# Cube_Robot.net
KiCad netlist of a schematic drawn in Altium Designer
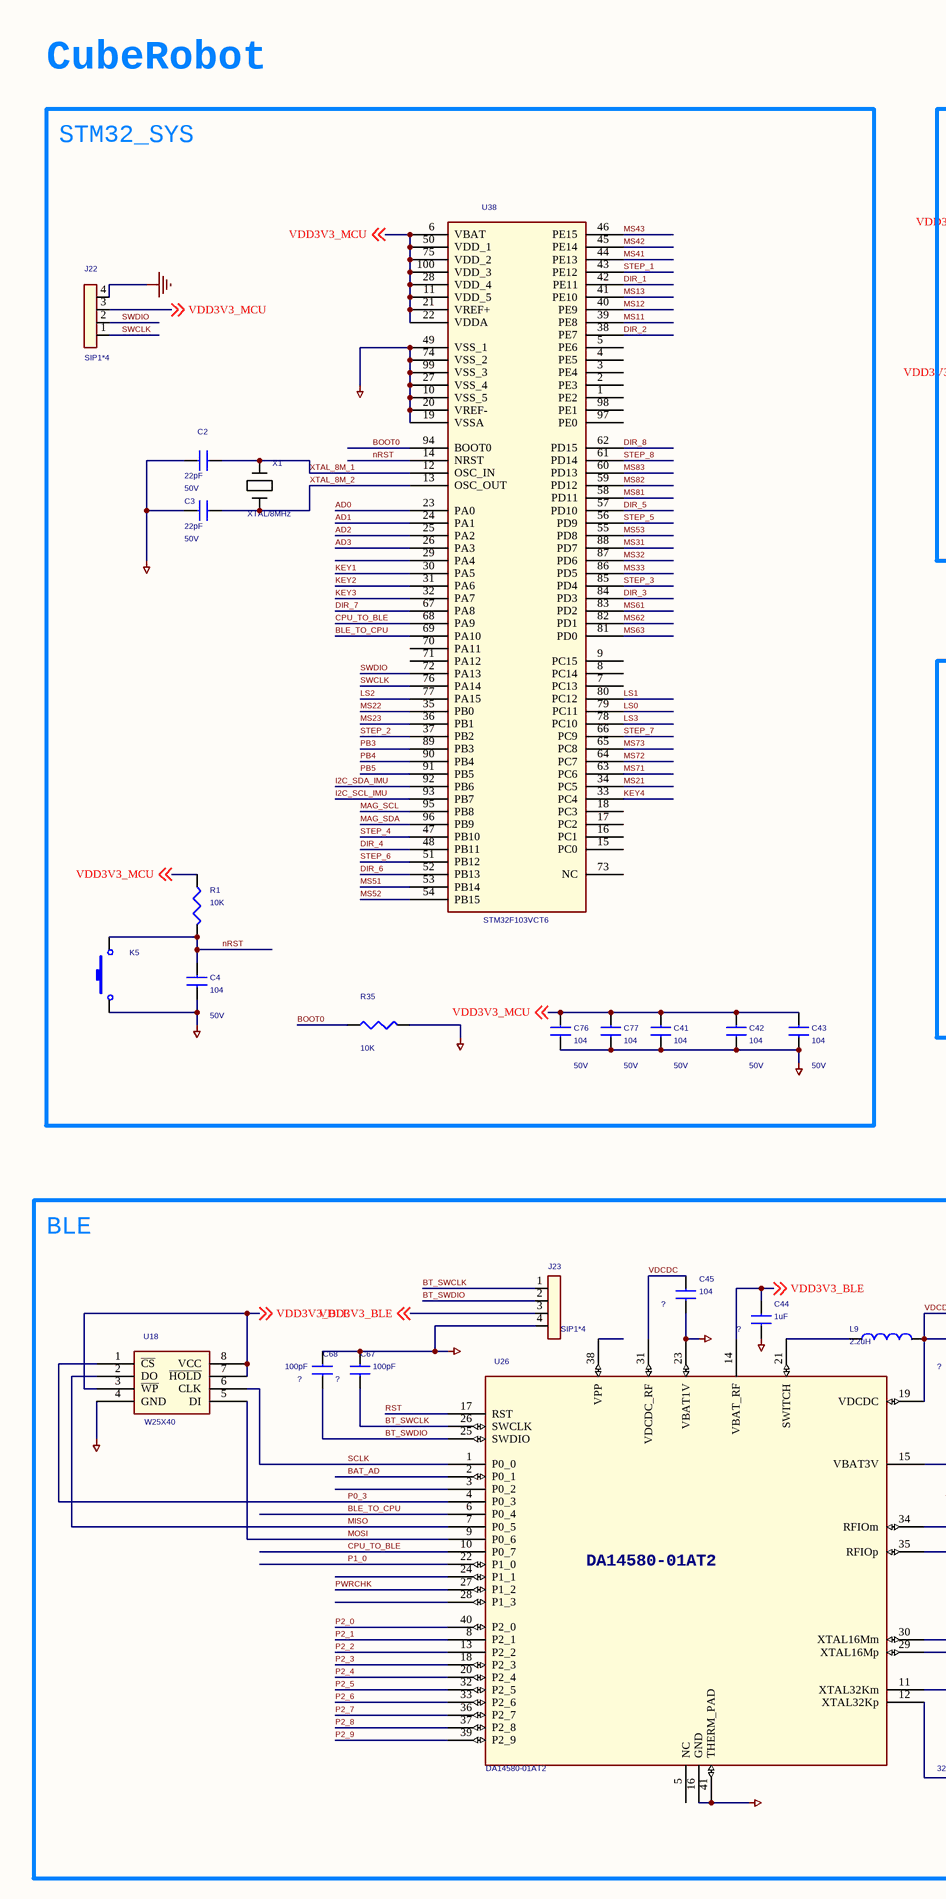
[diagram p0: Cube_Robot.SchDoc, left]
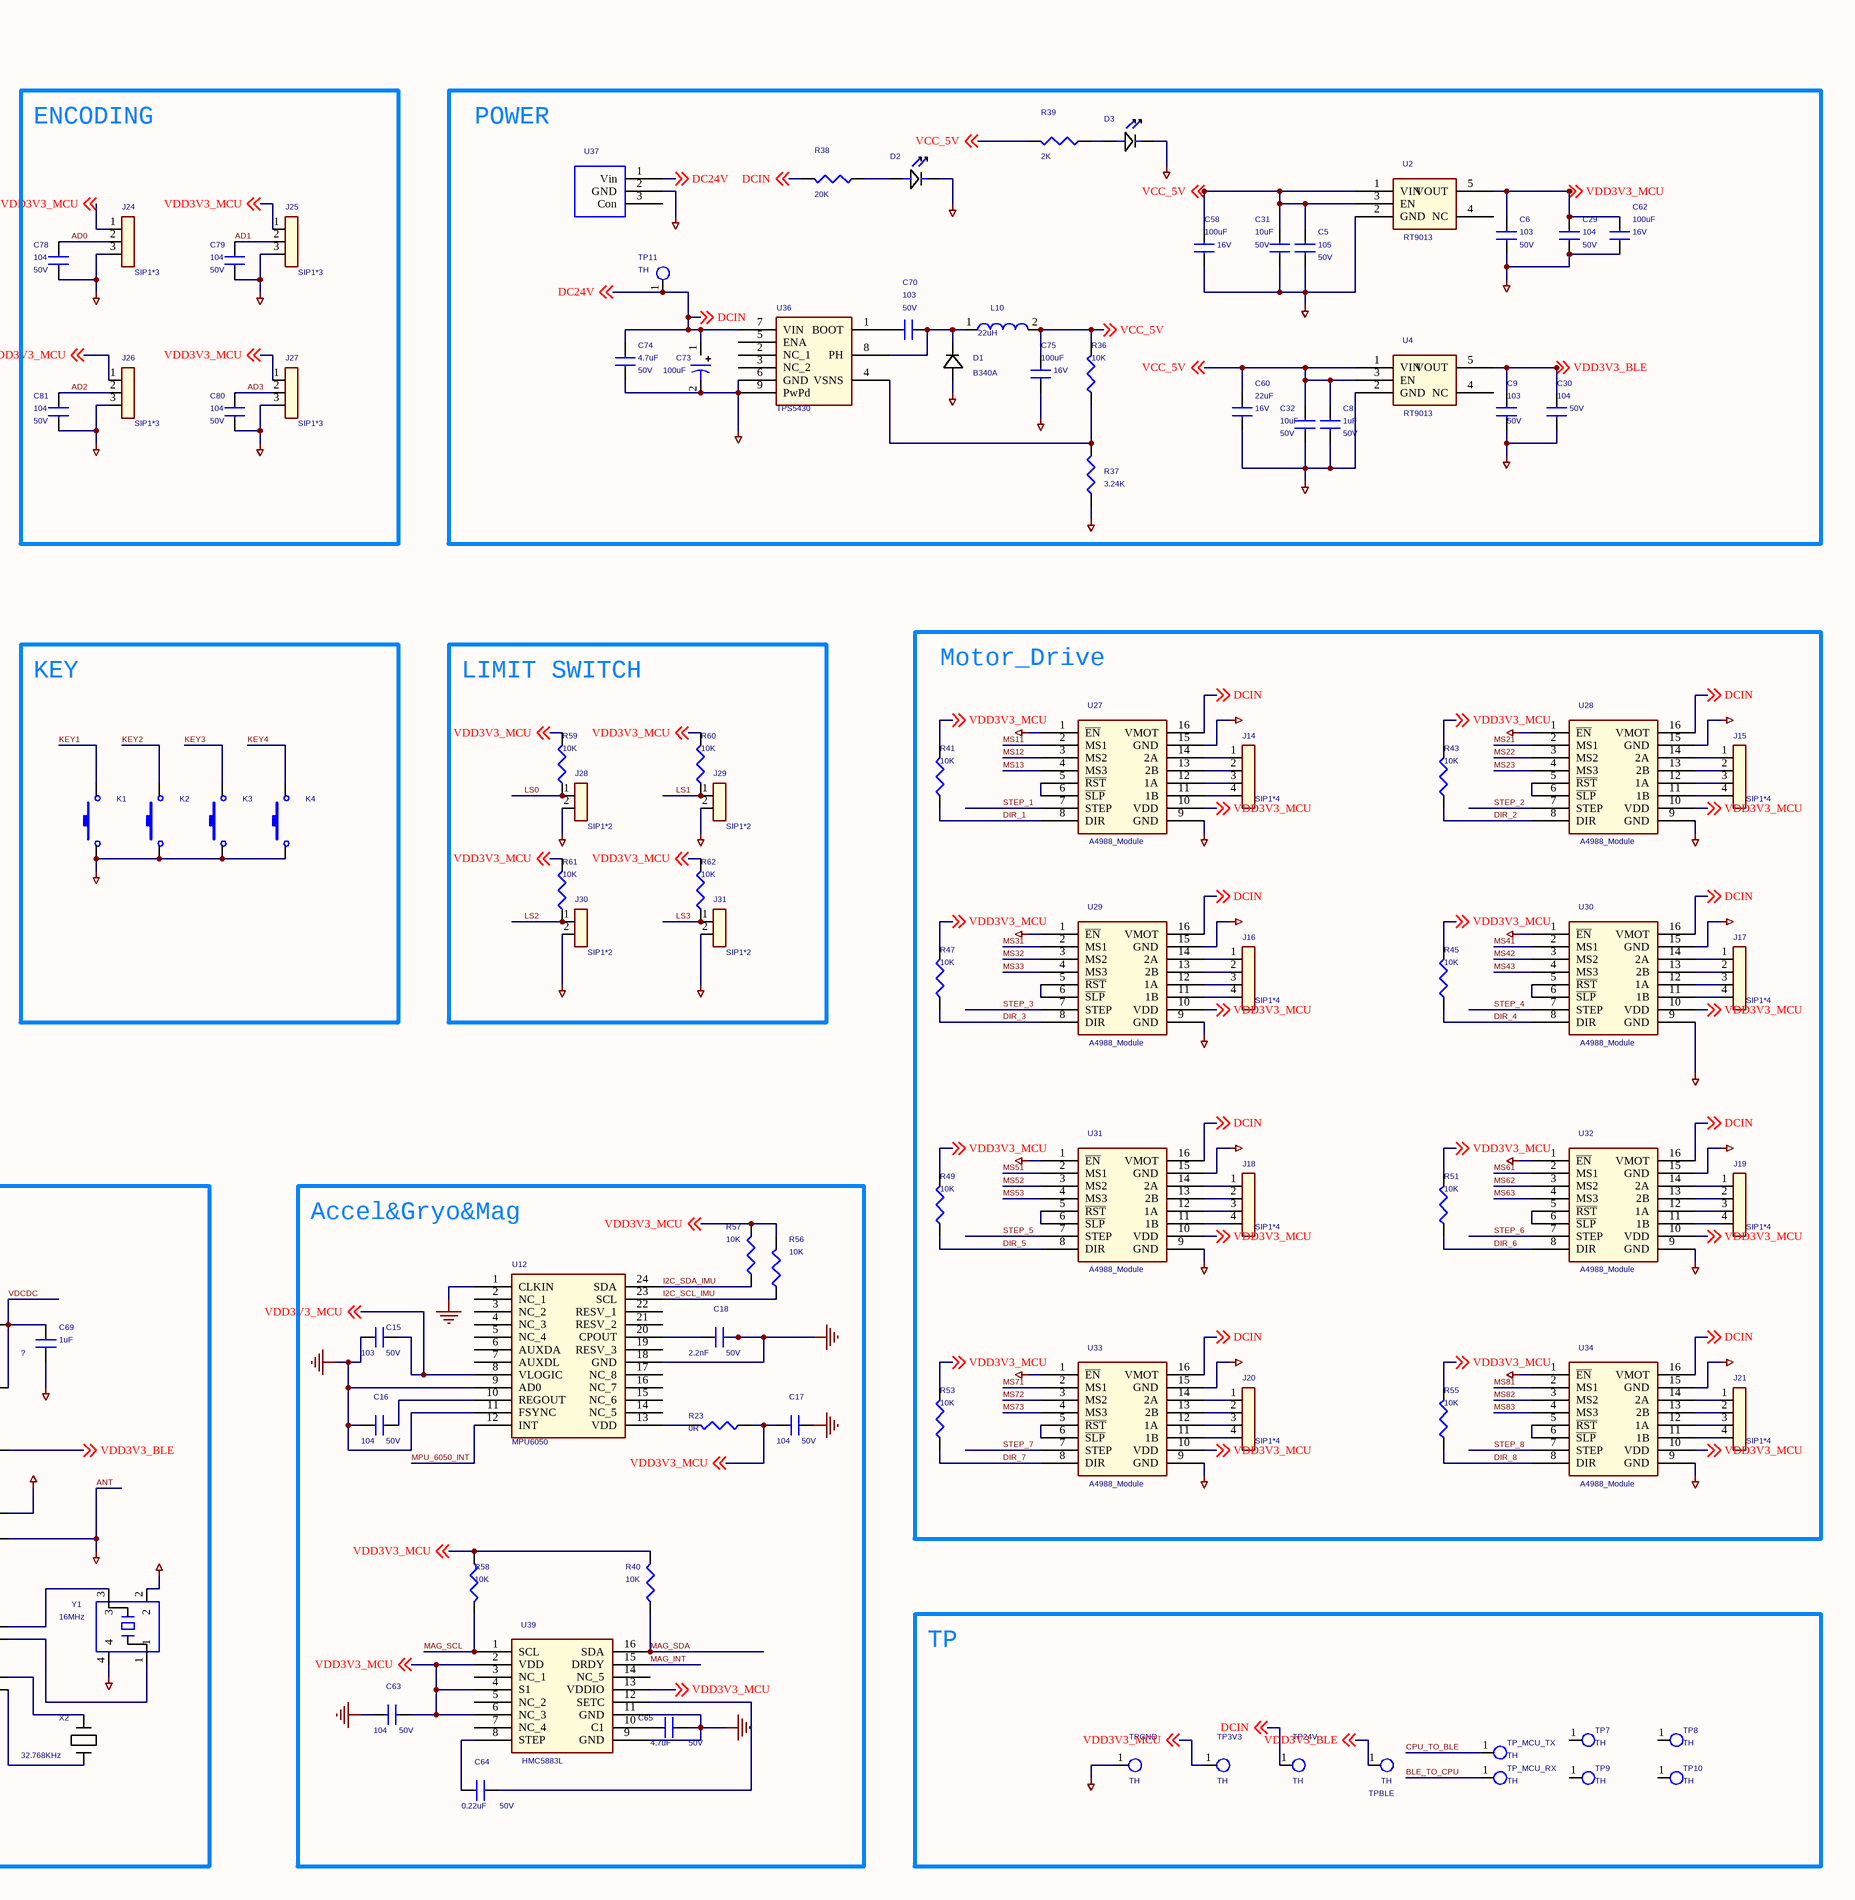
[diagram p1: Cube_Robot.SchDoc, right]

(export (version "E")
  (design (tool "Eeschema 10.0.6"))
  (components
    (comp (ref "C2")
      (value "22pF")
      (footprint "0603C")
      (fields (field (name "POWER CONSUMPTION") "50V"))
      (libsource (lib "*") (part "CAPNP"))
    )
    (comp (ref "C3")
      (value "22pF")
      (footprint "0603C")
      (fields (field (name "POWER CONSUMPTION") "50V"))
      (libsource (lib "*") (part "CAPNP"))
    )
    (comp (ref "C4")
      (value "104")
      (footprint "0603C")
      (fields (field (name "POWER CONSUMPTION") "50V"))
      (libsource (lib "*") (part "CAPNP"))
    )
    (comp (ref "C5")
      (value "105")
      (footprint "0603C")
      (fields (field (name "POWER CONSUMPTION") "50V"))
      (libsource (lib "*") (part "CAPNP"))
    )
    (comp (ref "C6")
      (value "103")
      (footprint "0603C")
      (fields (field (name "POWER CONSUMPTION") "50V"))
      (libsource (lib "*") (part "CAPNP"))
    )
    (comp (ref "C8")
      (value "1uF")
      (footprint "0603C")
      (fields (field (name "POWER CONSUMPTION") "50V"))
      (libsource (lib "*") (part "CAPNP"))
    )
    (comp (ref "C9")
      (value "103")
      (footprint "0603C")
      (fields (field (name "POWER CONSUMPTION") "50V"))
      (libsource (lib "*") (part "CAPNP"))
    )
    (comp (ref "C15")
      (value "103")
      (footprint "0603C")
      (fields (field (name "POWER CONSUMPTION") "50V"))
      (libsource (lib "*") (part "CAPNP"))
    )
    (comp (ref "C16")
      (value "104")
      (footprint "0603C")
      (fields (field (name "POWER CONSUMPTION") "50V"))
      (libsource (lib "*") (part "CAPNP"))
    )
    (comp (ref "C17")
      (value "104")
      (footprint "0603C")
      (fields (field (name "POWER CONSUMPTION") "50V"))
      (libsource (lib "*") (part "CAPNP"))
    )
    (comp (ref "C18")
      (value "2.2nF")
      (footprint "0603C")
      (fields (field (name "POWER CONSUMPTION") "50V"))
      (libsource (lib "*") (part "CAPNP"))
    )
    (comp (ref "C29")
      (value "104")
      (footprint "0603C")
      (fields (field (name "POWER CONSUMPTION") "50V"))
      (libsource (lib "*") (part "CAPNP"))
    )
    (comp (ref "C30")
      (value "104")
      (footprint "0603C")
      (fields (field (name "POWER CONSUMPTION") "50V"))
      (libsource (lib "*") (part "CAPNP"))
    )
    (comp (ref "C31")
      (value "10uF")
      (footprint "0603C")
      (fields (field (name "POWER CONSUMPTION") "50V"))
      (libsource (lib "*") (part "CAPNP"))
    )
    (comp (ref "C32")
      (value "10uF")
      (footprint "0603C")
      (fields (field (name "POWER CONSUMPTION") "50V"))
      (libsource (lib "*") (part "CAPNP"))
    )
    (comp (ref "C41")
      (value "104")
      (footprint "0603C")
      (fields (field (name "POWER CONSUMPTION") "50V"))
      (libsource (lib "*") (part "CAPNP"))
    )
    (comp (ref "C42")
      (value "104")
      (footprint "0603C")
      (fields (field (name "POWER CONSUMPTION") "50V"))
      (libsource (lib "*") (part "CAPNP"))
    )
    (comp (ref "C43")
      (value "104")
      (footprint "0603C")
      (fields (field (name "POWER CONSUMPTION") "50V"))
      (libsource (lib "*") (part "CAPNP"))
    )
    (comp (ref "C44")
      (value "1uF")
      (footprint "0603C")
      (fields (field (name "POWER CONSUMPTION") "?"))
      (libsource (lib "*") (part "CAPNP"))
    )
    (comp (ref "C45")
      (value "104")
      (footprint "0603C")
      (fields (field (name "POWER CONSUMPTION") "?"))
      (libsource (lib "*") (part "CAPNP"))
    )
    (comp (ref "C58")
      (value "100uF")
      (footprint "1206C")
      (fields (field (name "POWER CONSUMPTION") "16V"))
      (libsource (lib "*") (part "CAPNP"))
    )
    (comp (ref "C60")
      (value "22uF")
      (footprint "1206C")
      (fields (field (name "POWER CONSUMPTION") "16V"))
      (libsource (lib "*") (part "CAPNP"))
    )
    (comp (ref "C62")
      (value "100uF")
      (footprint "1206C")
      (fields (field (name "POWER CONSUMPTION") "16V"))
      (libsource (lib "*") (part "CAPNP"))
    )
    (comp (ref "C63")
      (value "104")
      (footprint "0603C")
      (fields (field (name "POWER CONSUMPTION") "50V"))
      (libsource (lib "*") (part "CAPNP"))
    )
    (comp (ref "C64")
      (value "0.22uF")
      (footprint "0603C")
      (fields (field (name "POWER CONSUMPTION") "50V"))
      (libsource (lib "*") (part "CAPNP"))
    )
    (comp (ref "C65")
      (value "4.7uF")
      (footprint "0603C")
      (fields (field (name "POWER CONSUMPTION") "50V"))
      (libsource (lib "*") (part "CAPNP"))
    )
    (comp (ref "C67")
      (value "100pF")
      (footprint "0603C")
      (fields (field (name "POWER CONSUMPTION") "?"))
      (libsource (lib "*") (part "CAPNP"))
    )
    (comp (ref "C68")
      (value "100pF")
      (footprint "0603C")
      (fields (field (name "POWER CONSUMPTION") "?"))
      (libsource (lib "*") (part "CAPNP"))
    )
    (comp (ref "C69")
      (value "1uF")
      (footprint "0603C")
      (fields (field (name "POWER CONSUMPTION") "?"))
      (libsource (lib "*") (part "CAPNP"))
    )
    (comp (ref "C70")
      (value "103")
      (footprint "0603C")
      (fields (field (name "POWER CONSUMPTION") "50V"))
      (libsource (lib "*") (part "CAPNP"))
    )
    (comp (ref "C73") (value "100uF") (footprint "贴片电解电容") (libsource (lib "*") (part "Capacitor2")))
    (comp (ref "C74")
      (value "4.7uF")
      (footprint "0603C")
      (fields (field (name "POWER CONSUMPTION") "50V"))
      (libsource (lib "*") (part "CAPNP"))
    )
    (comp (ref "C75")
      (value "100uF")
      (footprint "1206C")
      (fields (field (name "POWER CONSUMPTION") "16V"))
      (libsource (lib "*") (part "CAPNP"))
    )
    (comp (ref "C76")
      (value "104")
      (footprint "0603C")
      (fields (field (name "POWER CONSUMPTION") "50V"))
      (libsource (lib "*") (part "CAPNP"))
    )
    (comp (ref "C77")
      (value "104")
      (footprint "0603C")
      (fields (field (name "POWER CONSUMPTION") "50V"))
      (libsource (lib "*") (part "CAPNP"))
    )
    (comp (ref "C78")
      (value "104")
      (footprint "0603C")
      (fields (field (name "POWER CONSUMPTION") "50V"))
      (libsource (lib "*") (part "CAPNP"))
    )
    (comp (ref "C79")
      (value "104")
      (footprint "0603C")
      (fields (field (name "POWER CONSUMPTION") "50V"))
      (libsource (lib "*") (part "CAPNP"))
    )
    (comp (ref "C80")
      (value "104")
      (footprint "0603C")
      (fields (field (name "POWER CONSUMPTION") "50V"))
      (libsource (lib "*") (part "CAPNP"))
    )
    (comp (ref "C81")
      (value "104")
      (footprint "0603C")
      (fields (field (name "POWER CONSUMPTION") "50V"))
      (libsource (lib "*") (part "CAPNP"))
    )
    (comp (ref "D1") (value "B340A") (footprint "IN4148") (libsource (lib "*") (part "DIODE")))
    (comp (ref "D2") (value "LED") (footprint "0805") (libsource (lib "*") (part "LED")))
    (comp (ref "D3") (value "LED") (footprint "0805") (libsource (lib "*") (part "LED")))
    (comp (ref "J14") (value "SIP1*4") (footprint "DIP1x4") (libsource (lib "*") (part "DIP1x4")))
    (comp (ref "J15") (value "SIP1*4") (footprint "DIP1x4") (libsource (lib "*") (part "DIP1x4")))
    (comp (ref "J16") (value "SIP1*4") (footprint "DIP1x4") (libsource (lib "*") (part "DIP1x4")))
    (comp (ref "J17") (value "SIP1*4") (footprint "DIP1x4") (libsource (lib "*") (part "DIP1x4")))
    (comp (ref "J18") (value "SIP1*4") (footprint "DIP1x4") (libsource (lib "*") (part "DIP1x4")))
    (comp (ref "J19") (value "SIP1*4") (footprint "DIP1x4") (libsource (lib "*") (part "DIP1x4")))
    (comp (ref "J20") (value "SIP1*4") (footprint "DIP1x4") (libsource (lib "*") (part "DIP1x4")))
    (comp (ref "J21") (value "SIP1*4") (footprint "DIP1x4") (libsource (lib "*") (part "DIP1x4")))
    (comp (ref "J22") (value "SIP1*4") (footprint "DIP1x4") (libsource (lib "") (part "DIP1x4_1")))
    (comp (ref "J23") (value "SIP1*4") (footprint "DIP1x4") (libsource (lib "*") (part "DIP1x4")))
    (comp (ref "J24") (value "SIP1*3") (footprint "DIP1x3") (libsource (lib "*") (part "DIP1x3")))
    (comp (ref "J25") (value "SIP1*3") (footprint "DIP1x3") (libsource (lib "*") (part "DIP1x3")))
    (comp (ref "J26") (value "SIP1*3") (footprint "DIP1x3") (libsource (lib "*") (part "DIP1x3")))
    (comp (ref "J27") (value "SIP1*3") (footprint "DIP1x3") (libsource (lib "*") (part "DIP1x3")))
    (comp (ref "J28") (value "SIP1*2") (footprint "SIP-2-2R5") (libsource (lib "*") (part "SIP-2")))
    (comp (ref "J29") (value "SIP1*2") (footprint "SIP-2-2R5") (libsource (lib "*") (part "SIP-2")))
    (comp (ref "J30") (value "SIP1*2") (footprint "SIP-2-2R5") (libsource (lib "*") (part "SIP-2")))
    (comp (ref "J31") (value "SIP1*2") (footprint "SIP-2-2R5") (libsource (lib "*") (part "SIP-2")))
    (comp (ref "K1") (value "KEY") (footprint "侧向贴片按键") (libsource (lib "*") (part "KEY")))
    (comp (ref "K2") (value "KEY") (footprint "侧向贴片按键") (libsource (lib "*") (part "KEY")))
    (comp (ref "K3") (value "KEY") (footprint "侧向贴片按键") (libsource (lib "*") (part "KEY")))
    (comp (ref "K4") (value "KEY") (footprint "侧向贴片按键") (libsource (lib "*") (part "KEY")))
    (comp (ref "K5") (value "KEY") (footprint "侧向贴片按键") (libsource (lib "*") (part "KEY")))
    (comp (ref "L9")
      (value "2.2uH")
      (footprint "cl0707m")
      (fields (field (name "PART NUMBER") "1.6.LI-1105-A0"))
      (libsource (lib "*") (part "IND"))
    )
    (comp (ref "L10") (value "22uH") (footprint "大电感") (libsource (lib "*") (part "Inductor")))
    (comp (ref "R1")
      (value "10K")
      (footprint "0603R")
      (fields (field (name "PART NUMBER") "1.3.1.RS-0011-70"))
      (libsource (lib "*") (part "RESSMD"))
    )
    (comp (ref "R23")
      (value "0R")
      (footprint "0603R")
      (fields (field (name "PART NUMBER") "1.3.1.RS-0011-70"))
      (libsource (lib "*") (part "RESSMD"))
    )
    (comp (ref "R35")
      (value "10K")
      (footprint "0603R")
      (fields (field (name "PART NUMBER") "1.3.1.RS-0011-70"))
      (libsource (lib "*") (part "RESSMD"))
    )
    (comp (ref "R36")
      (value "10K")
      (footprint "0603R")
      (fields (field (name "PART NUMBER") "1.3.1.RS-0011-70"))
      (libsource (lib "*") (part "RESSMD"))
    )
    (comp (ref "R37")
      (value "3.24K")
      (footprint "0805R")
      (fields (field (name "PART NUMBER") "1.3.1.RS-0011-70"))
      (libsource (lib "*") (part "RESSMD"))
    )
    (comp (ref "R38")
      (value "20K")
      (footprint "0603R")
      (fields (field (name "PART NUMBER") "1.3.1.RS-0011-70"))
      (libsource (lib "*") (part "RESSMD"))
    )
    (comp (ref "R39")
      (value "2K")
      (footprint "0603R")
      (fields (field (name "PART NUMBER") "1.3.1.RS-0011-70"))
      (libsource (lib "*") (part "RESSMD"))
    )
    (comp (ref "R40")
      (value "10K")
      (footprint "0603R")
      (fields (field (name "PART NUMBER") "1.3.1.RS-0011-70"))
      (libsource (lib "*") (part "RESSMD"))
    )
    (comp (ref "R41")
      (value "10K")
      (footprint "0603R")
      (fields (field (name "PART NUMBER") "1.3.1.RS-0011-70"))
      (libsource (lib "*") (part "RESSMD"))
    )
    (comp (ref "R43")
      (value "10K")
      (footprint "0603R")
      (fields (field (name "PART NUMBER") "1.3.1.RS-0011-70"))
      (libsource (lib "*") (part "RESSMD"))
    )
    (comp (ref "R45")
      (value "10K")
      (footprint "0603R")
      (fields (field (name "PART NUMBER") "1.3.1.RS-0011-70"))
      (libsource (lib "*") (part "RESSMD"))
    )
    (comp (ref "R47")
      (value "10K")
      (footprint "0603R")
      (fields (field (name "PART NUMBER") "1.3.1.RS-0011-70"))
      (libsource (lib "*") (part "RESSMD"))
    )
    (comp (ref "R49")
      (value "10K")
      (footprint "0603R")
      (fields (field (name "PART NUMBER") "1.3.1.RS-0011-70"))
      (libsource (lib "*") (part "RESSMD"))
    )
    (comp (ref "R51")
      (value "10K")
      (footprint "0603R")
      (fields (field (name "PART NUMBER") "1.3.1.RS-0011-70"))
      (libsource (lib "*") (part "RESSMD"))
    )
    (comp (ref "R53")
      (value "10K")
      (footprint "0603R")
      (fields (field (name "PART NUMBER") "1.3.1.RS-0011-70"))
      (libsource (lib "*") (part "RESSMD"))
    )
    (comp (ref "R55")
      (value "10K")
      (footprint "0603R")
      (fields (field (name "PART NUMBER") "1.3.1.RS-0011-70"))
      (libsource (lib "*") (part "RESSMD"))
    )
    (comp (ref "R56")
      (value "10K")
      (footprint "0603R")
      (fields (field (name "PART NUMBER") "1.3.1.RS-0011-70"))
      (libsource (lib "*") (part "RESSMD"))
    )
    (comp (ref "R57")
      (value "10K")
      (footprint "0603R")
      (fields (field (name "PART NUMBER") "1.3.1.RS-0011-70"))
      (libsource (lib "*") (part "RESSMD"))
    )
    (comp (ref "R58")
      (value "10K")
      (footprint "0603R")
      (fields (field (name "PART NUMBER") "1.3.1.RS-0011-70"))
      (libsource (lib "*") (part "RESSMD"))
    )
    (comp (ref "R59")
      (value "10K")
      (footprint "0603R")
      (fields (field (name "PART NUMBER") "1.3.1.RS-0011-70"))
      (libsource (lib "*") (part "RESSMD"))
    )
    (comp (ref "R60")
      (value "10K")
      (footprint "0603R")
      (fields (field (name "PART NUMBER") "1.3.1.RS-0011-70"))
      (libsource (lib "*") (part "RESSMD"))
    )
    (comp (ref "R61")
      (value "10K")
      (footprint "0603R")
      (fields (field (name "PART NUMBER") "1.3.1.RS-0011-70"))
      (libsource (lib "*") (part "RESSMD"))
    )
    (comp (ref "R62")
      (value "10K")
      (footprint "0603R")
      (fields (field (name "PART NUMBER") "1.3.1.RS-0011-70"))
      (libsource (lib "*") (part "RESSMD"))
    )
    (comp (ref "TP3V3") (value "TH") (footprint "TP_TH") (libsource (lib "*") (part "TP")))
    (comp (ref "TP7") (value "TH") (footprint "HOLES-3R00") (libsource (lib "*") (part "TP")))
    (comp (ref "TP8") (value "TH") (footprint "HOLES-3R00") (libsource (lib "*") (part "TP")))
    (comp (ref "TP9") (value "TH") (footprint "HOLES-3R00") (libsource (lib "*") (part "TP")))
    (comp (ref "TP10") (value "TH") (footprint "HOLES-3R00") (libsource (lib "*") (part "TP")))
    (comp (ref "TP11") (value "TH") (footprint "TP_TH") (libsource (lib "*") (part "TP")))
    (comp (ref "TP24V") (value "TH") (footprint "TP_TH") (libsource (lib "*") (part "TP")))
    (comp (ref "TPBLE") (value "TH") (footprint "TP_TH") (libsource (lib "*") (part "TP")))
    (comp (ref "TPGND") (value "TH") (footprint "TP_TH") (libsource (lib "*") (part "TP")))
    (comp (ref "TP_MCU_RX") (value "TH") (footprint "TP_TH") (libsource (lib "*") (part "TP")))
    (comp (ref "TP_MCU_TX") (value "TH") (footprint "TP_TH") (libsource (lib "*") (part "TP")))
    (comp (ref "U2") (value "RT9013") (footprint "SOT23-5") (libsource (lib "*") (part "RT9013")))
    (comp (ref "U4") (value "RT9013") (footprint "SOT23-5") (libsource (lib "*") (part "RT9013")))
    (comp (ref "U12") (value "MPU6050") (footprint "QFN24") (libsource (lib "*") (part "MPU6050")))
    (comp (ref "U18") (value "W25X40") (footprint "SOP8_NOPAD") (libsource (lib "*") (part "W25X40CL")))
    (comp (ref "U26")
      (value "DA14580-01AT2")
      (footprint "QFN40_5_5")
      (libsource (lib "*") (part "DA14580-01AT2"))
    )
    (comp (ref "U27") (value "A4988_Module") (footprint "A4988") (libsource (lib "*") (part "A4988_Module")))
    (comp (ref "U28") (value "A4988_Module") (footprint "A4988") (libsource (lib "*") (part "A4988_Module")))
    (comp (ref "U29") (value "A4988_Module") (footprint "A4988") (libsource (lib "*") (part "A4988_Module")))
    (comp (ref "U30") (value "A4988_Module") (footprint "A4988") (libsource (lib "*") (part "A4988_Module")))
    (comp (ref "U31") (value "A4988_Module") (footprint "A4988") (libsource (lib "*") (part "A4988_Module")))
    (comp (ref "U32") (value "A4988_Module") (footprint "A4988") (libsource (lib "*") (part "A4988_Module")))
    (comp (ref "U33") (value "A4988_Module") (footprint "A4988") (libsource (lib "*") (part "A4988_Module")))
    (comp (ref "U34") (value "A4988_Module") (footprint "A4988") (libsource (lib "*") (part "A4988_Module")))
    (comp (ref "U36") (value "TPS5430") (footprint "SOP8") (libsource (lib "*") (part "tps5430")))
    (comp (ref "U37") (value "DC005") (footprint "DC005") (libsource (lib "*") (part "DC005")))
    (comp (ref "U38")
      (value "STM32F103VCT6")
      (footprint "LQFP100")
      (libsource (lib "*") (part "STM32F103VXT6"))
    )
    (comp (ref "U39") (value "HMC5883L") (footprint "HMC5883L") (libsource (lib "*") (part "HMC5883L")))
    (comp (ref "X1") (value "XTAL/8MHz") (footprint "XTAL_3x8") (libsource (lib "*") (part "XTAL")))
    (comp (ref "X2") (value "32.768KHz") (footprint "XTAL_3x8") (libsource (lib "*") (part "XTAL")))
    (comp (ref "Y1") (value "16MHz") (footprint "smd_32768hz") (libsource (lib "*") (part "OSC3225")))
  )
  (nets
    (net (code "1") (name "/AD0") (class "Default")
      (node (ref "C78") (pin "2") (pinfunction "2_2") (pintype "passive"))
      (node (ref "J24") (pin "2") (pinfunction "2_2") (pintype "passive"))
      (node (ref "U38") (pin "23") (pinfunction "PA0_23") (pintype "passive"))
    )
    (net (code "2") (name "/AD1") (class "Default")
      (node (ref "C79") (pin "2") (pinfunction "2_2") (pintype "passive"))
      (node (ref "J25") (pin "2") (pinfunction "2_2") (pintype "passive"))
      (node (ref "U38") (pin "24") (pinfunction "PA1_24") (pintype "passive"))
    )
    (net (code "3") (name "/AD2") (class "Default")
      (node (ref "C81") (pin "2") (pinfunction "2_2") (pintype "passive"))
      (node (ref "J26") (pin "2") (pinfunction "2_2") (pintype "passive"))
      (node (ref "U38") (pin "25") (pinfunction "PA2_25") (pintype "passive"))
    )
    (net (code "4") (name "/AD3") (class "Default")
      (node (ref "C80") (pin "2") (pinfunction "2_2") (pintype "passive"))
      (node (ref "J27") (pin "2") (pinfunction "2_2") (pintype "passive"))
      (node (ref "U38") (pin "26") (pinfunction "PA3_26") (pintype "passive"))
    )
    (net (code "5") (name "/BAT_AD") (class "Default")
      (node (ref "U26") (pin "2") (pinfunction "P0_1_2") (pintype "bidirectional"))
    )
    (net (code "6") (name "/BLE_TO_CPU") (class "Default")
      (node (ref "TP_MCU_RX") (pin "1") (pinfunction "1_1") (pintype "passive"))
      (node (ref "U26") (pin "6") (pinfunction "P0_4_6") (pintype "passive"))
      (node (ref "U38") (pin "69") (pinfunction "PA10_69") (pintype "passive"))
    )
    (net (code "7") (name "/BOOT0") (class "Default")
      (node (ref "R35") (pin "1") (pinfunction "1_1") (pintype "passive"))
      (node (ref "U38") (pin "94") (pinfunction "BOOT0_94") (pintype "passive"))
    )
    (net (code "8") (name "/BT_SWCLK") (class "Default")
      (node (ref "C67") (pin "2") (pinfunction "2_2") (pintype "passive"))
      (node (ref "J23") (pin "1") (pinfunction "1_1") (pintype "passive"))
      (node (ref "U26") (pin "26") (pinfunction "SWCLK_26") (pintype "bidirectional"))
    )
    (net (code "9") (name "/BT_SWDIO") (class "Default")
      (node (ref "C68") (pin "2") (pinfunction "2_2") (pintype "passive"))
      (node (ref "J23") (pin "2") (pinfunction "2_2") (pintype "passive"))
      (node (ref "U26") (pin "25") (pinfunction "SWDIO_25") (pintype "bidirectional"))
    )
    (net (code "10") (name "/CPU_TO_BLE") (class "Default")
      (node (ref "TP_MCU_TX") (pin "1") (pinfunction "1_1") (pintype "passive"))
      (node (ref "U26") (pin "10") (pinfunction "P0_7_10") (pintype "passive"))
      (node (ref "U38") (pin "68") (pinfunction "PA9_68") (pintype "passive"))
    )
    (net (code "11") (name "/DIR_1") (class "Default")
      (node (ref "R41") (pin "1") (pinfunction "1_1") (pintype "passive"))
      (node (ref "U27") (pin "8") (pinfunction "DIR_8") (pintype "passive"))
      (node (ref "U38") (pin "42") (pinfunction "PE11_42") (pintype "passive"))
    )
    (net (code "12") (name "/DIR_2") (class "Default")
      (node (ref "R43") (pin "1") (pinfunction "1_1") (pintype "passive"))
      (node (ref "U28") (pin "8") (pinfunction "DIR_8") (pintype "passive"))
      (node (ref "U38") (pin "38") (pinfunction "PE7_38") (pintype "passive"))
    )
    (net (code "13") (name "/DIR_3") (class "Default")
      (node (ref "R47") (pin "1") (pinfunction "1_1") (pintype "passive"))
      (node (ref "U29") (pin "8") (pinfunction "DIR_8") (pintype "passive"))
      (node (ref "U38") (pin "84") (pinfunction "PD3_84") (pintype "passive"))
    )
    (net (code "14") (name "/DIR_4") (class "Default")
      (node (ref "R45") (pin "1") (pinfunction "1_1") (pintype "passive"))
      (node (ref "U30") (pin "8") (pinfunction "DIR_8") (pintype "passive"))
      (node (ref "U38") (pin "48") (pinfunction "PB11_48") (pintype "passive"))
    )
    (net (code "15") (name "/DIR_5") (class "Default")
      (node (ref "R49") (pin "1") (pinfunction "1_1") (pintype "passive"))
      (node (ref "U31") (pin "8") (pinfunction "DIR_8") (pintype "passive"))
      (node (ref "U38") (pin "57") (pinfunction "PD10_57") (pintype "passive"))
    )
    (net (code "16") (name "/DIR_6") (class "Default")
      (node (ref "R51") (pin "1") (pinfunction "1_1") (pintype "passive"))
      (node (ref "U32") (pin "8") (pinfunction "DIR_8") (pintype "passive"))
      (node (ref "U38") (pin "52") (pinfunction "PB13_52") (pintype "passive"))
    )
    (net (code "17") (name "/DIR_7") (class "Default")
      (node (ref "R53") (pin "1") (pinfunction "1_1") (pintype "passive"))
      (node (ref "U33") (pin "8") (pinfunction "DIR_8") (pintype "passive"))
      (node (ref "U38") (pin "67") (pinfunction "PA8_67") (pintype "passive"))
    )
    (net (code "18") (name "/DIR_8") (class "Default")
      (node (ref "R55") (pin "1") (pinfunction "1_1") (pintype "passive"))
      (node (ref "U34") (pin "8") (pinfunction "DIR_8") (pintype "passive"))
      (node (ref "U38") (pin "62") (pinfunction "PD15_62") (pintype "passive"))
    )
    (net (code "19") (name "/I2C_SCL_IMU") (class "Default")
      (node (ref "R56") (pin "1") (pinfunction "1_1") (pintype "passive"))
      (node (ref "U12") (pin "23") (pinfunction "SCL_23") (pintype "passive"))
      (node (ref "U38") (pin "93") (pinfunction "PB7_93") (pintype "passive"))
    )
    (net (code "20") (name "/I2C_SDA_IMU") (class "Default")
      (node (ref "R57") (pin "1") (pinfunction "1_1") (pintype "passive"))
      (node (ref "U12") (pin "24") (pinfunction "SDA_24") (pintype "passive"))
      (node (ref "U38") (pin "92") (pinfunction "PB6_92") (pintype "passive"))
    )
    (net (code "21") (name "/KEY1") (class "Default")
      (node (ref "K1") (pin "2") (pinfunction "2_2") (pintype "passive"))
      (node (ref "U38") (pin "30") (pinfunction "PA5_30") (pintype "passive"))
    )
    (net (code "22") (name "/KEY2") (class "Default")
      (node (ref "K2") (pin "2") (pinfunction "2_2") (pintype "passive"))
      (node (ref "U38") (pin "31") (pinfunction "PA6_31") (pintype "passive"))
    )
    (net (code "23") (name "/KEY3") (class "Default")
      (node (ref "K3") (pin "2") (pinfunction "2_2") (pintype "passive"))
      (node (ref "U38") (pin "32") (pinfunction "PA7_32") (pintype "passive"))
    )
    (net (code "24") (name "/KEY4") (class "Default")
      (node (ref "K4") (pin "2") (pinfunction "2_2") (pintype "passive"))
      (node (ref "U38") (pin "33") (pinfunction "PC4_33") (pintype "passive"))
    )
    (net (code "25") (name "/LS0") (class "Default")
      (node (ref "J28") (pin "1") (pinfunction "1_1") (pintype "passive"))
      (node (ref "R59") (pin "1") (pinfunction "1_1") (pintype "passive"))
      (node (ref "U38") (pin "79") (pinfunction "PC11_79") (pintype "passive"))
    )
    (net (code "26") (name "/LS1") (class "Default")
      (node (ref "J29") (pin "1") (pinfunction "1_1") (pintype "passive"))
      (node (ref "R60") (pin "1") (pinfunction "1_1") (pintype "passive"))
      (node (ref "U38") (pin "80") (pinfunction "PC12_80") (pintype "passive"))
    )
    (net (code "27") (name "/LS2") (class "Default")
      (node (ref "J30") (pin "1") (pinfunction "1_1") (pintype "passive"))
      (node (ref "R61") (pin "1") (pinfunction "1_1") (pintype "passive"))
      (node (ref "U38") (pin "77") (pinfunction "PA15_77") (pintype "passive"))
    )
    (net (code "28") (name "/LS3") (class "Default")
      (node (ref "J31") (pin "1") (pinfunction "1_1") (pintype "passive"))
      (node (ref "R62") (pin "1") (pinfunction "1_1") (pintype "passive"))
      (node (ref "U38") (pin "78") (pinfunction "PC10_78") (pintype "passive"))
    )
    (net (code "29") (name "/MAG_INT") (class "Default")
      (node (ref "U39") (pin "15") (pinfunction "DRDY_15") (pintype "passive"))
    )
    (net (code "30") (name "/MAG_SCL") (class "Default")
      (node (ref "R58") (pin "2") (pinfunction "2_2") (pintype "passive"))
      (node (ref "U38") (pin "95") (pinfunction "PB8_95") (pintype "passive"))
      (node (ref "U39") (pin "1") (pinfunction "SCL_1") (pintype "passive"))
    )
    (net (code "31") (name "/MAG_SDA") (class "Default")
      (node (ref "R40") (pin "1") (pinfunction "1_1") (pintype "passive"))
      (node (ref "U38") (pin "96") (pinfunction "PB9_96") (pintype "passive"))
      (node (ref "U39") (pin "16") (pinfunction "SDA_16") (pintype "passive"))
    )
    (net (code "32") (name "/MISO") (class "Default")
      (node (ref "U18") (pin "2") (pinfunction "DO_2") (pintype "passive"))
      (node (ref "U26") (pin "7") (pinfunction "P0_5_7") (pintype "passive"))
    )
    (net (code "33") (name "/MOSI") (class "Default")
      (node (ref "U18") (pin "5") (pinfunction "DI_5") (pintype "passive"))
      (node (ref "U26") (pin "9") (pinfunction "P0_6_9") (pintype "passive"))
    )
    (net (code "34") (name "/MPU_6050_INT") (class "Default")
      (node (ref "U12") (pin "12") (pinfunction "INT_12") (pintype "passive"))
    )
    (net (code "35") (name "/MS11") (class "Default")
      (node (ref "U27") (pin "2") (pinfunction "MS1_2") (pintype "passive"))
      (node (ref "U38") (pin "39") (pinfunction "PE8_39") (pintype "passive"))
    )
    (net (code "36") (name "/MS12") (class "Default")
      (node (ref "U27") (pin "3") (pinfunction "MS2_3") (pintype "passive"))
      (node (ref "U38") (pin "40") (pinfunction "PE9_40") (pintype "passive"))
    )
    (net (code "37") (name "/MS13") (class "Default")
      (node (ref "U27") (pin "4") (pinfunction "MS3_4") (pintype "passive"))
      (node (ref "U38") (pin "41") (pinfunction "PE10_41") (pintype "passive"))
    )
    (net (code "38") (name "/MS21") (class "Default")
      (node (ref "U28") (pin "2") (pinfunction "MS1_2") (pintype "passive"))
      (node (ref "U38") (pin "34") (pinfunction "PC5_34") (pintype "passive"))
    )
    (net (code "39") (name "/MS22") (class "Default")
      (node (ref "U28") (pin "3") (pinfunction "MS2_3") (pintype "passive"))
      (node (ref "U38") (pin "35") (pinfunction "PB0_35") (pintype "passive"))
    )
    (net (code "40") (name "/MS23") (class "Default")
      (node (ref "U28") (pin "4") (pinfunction "MS3_4") (pintype "passive"))
      (node (ref "U38") (pin "36") (pinfunction "PB1_36") (pintype "passive"))
    )
    (net (code "41") (name "/MS31") (class "Default")
      (node (ref "U29") (pin "2") (pinfunction "MS1_2") (pintype "passive"))
      (node (ref "U38") (pin "88") (pinfunction "PD7_88") (pintype "passive"))
    )
    (net (code "42") (name "/MS32") (class "Default")
      (node (ref "U29") (pin "3") (pinfunction "MS2_3") (pintype "passive"))
      (node (ref "U38") (pin "87") (pinfunction "PD6_87") (pintype "passive"))
    )
    (net (code "43") (name "/MS33") (class "Default")
      (node (ref "U29") (pin "4") (pinfunction "MS3_4") (pintype "passive"))
      (node (ref "U38") (pin "86") (pinfunction "PD5_86") (pintype "passive"))
    )
    (net (code "44") (name "/MS41") (class "Default")
      (node (ref "U30") (pin "2") (pinfunction "MS1_2") (pintype "passive"))
      (node (ref "U38") (pin "44") (pinfunction "PE13_44") (pintype "passive"))
    )
    (net (code "45") (name "/MS42") (class "Default")
      (node (ref "U30") (pin "3") (pinfunction "MS2_3") (pintype "passive"))
      (node (ref "U38") (pin "45") (pinfunction "PE14_45") (pintype "passive"))
    )
    (net (code "46") (name "/MS43") (class "Default")
      (node (ref "U30") (pin "4") (pinfunction "MS3_4") (pintype "passive"))
      (node (ref "U38") (pin "46") (pinfunction "PE15_46") (pintype "passive"))
    )
    (net (code "47") (name "/MS51") (class "Default")
      (node (ref "U31") (pin "2") (pinfunction "MS1_2") (pintype "passive"))
      (node (ref "U38") (pin "53") (pinfunction "PB14_53") (pintype "passive"))
    )
    (net (code "48") (name "/MS52") (class "Default")
      (node (ref "U31") (pin "3") (pinfunction "MS2_3") (pintype "passive"))
      (node (ref "U38") (pin "54") (pinfunction "PB15_54") (pintype "passive"))
    )
    (net (code "49") (name "/MS53") (class "Default")
      (node (ref "U31") (pin "4") (pinfunction "MS3_4") (pintype "passive"))
      (node (ref "U38") (pin "55") (pinfunction "PD8_55") (pintype "passive"))
    )
    (net (code "50") (name "/MS61") (class "Default")
      (node (ref "U32") (pin "2") (pinfunction "MS1_2") (pintype "passive"))
      (node (ref "U38") (pin "83") (pinfunction "PD2_83") (pintype "passive"))
    )
    (net (code "51") (name "/MS62") (class "Default")
      (node (ref "U32") (pin "3") (pinfunction "MS2_3") (pintype "passive"))
      (node (ref "U38") (pin "82") (pinfunction "PD1_82") (pintype "passive"))
    )
    (net (code "52") (name "/MS63") (class "Default")
      (node (ref "U32") (pin "4") (pinfunction "MS3_4") (pintype "passive"))
      (node (ref "U38") (pin "81") (pinfunction "PD0_81") (pintype "passive"))
    )
    (net (code "53") (name "/MS71") (class "Default")
      (node (ref "U33") (pin "2") (pinfunction "MS1_2") (pintype "passive"))
      (node (ref "U38") (pin "63") (pinfunction "PC6_63") (pintype "passive"))
    )
    (net (code "54") (name "/MS72") (class "Default")
      (node (ref "U33") (pin "3") (pinfunction "MS2_3") (pintype "passive"))
      (node (ref "U38") (pin "64") (pinfunction "PC7_64") (pintype "passive"))
    )
    (net (code "55") (name "/MS73") (class "Default")
      (node (ref "U33") (pin "4") (pinfunction "MS3_4") (pintype "passive"))
      (node (ref "U38") (pin "65") (pinfunction "PC8_65") (pintype "passive"))
    )
    (net (code "56") (name "/MS81") (class "Default")
      (node (ref "U34") (pin "2") (pinfunction "MS1_2") (pintype "passive"))
      (node (ref "U38") (pin "58") (pinfunction "PD11_58") (pintype "passive"))
    )
    (net (code "57") (name "/MS82") (class "Default")
      (node (ref "U34") (pin "3") (pinfunction "MS2_3") (pintype "passive"))
      (node (ref "U38") (pin "59") (pinfunction "PD12_59") (pintype "passive"))
    )
    (net (code "58") (name "/MS83") (class "Default")
      (node (ref "U34") (pin "4") (pinfunction "MS3_4") (pintype "passive"))
      (node (ref "U38") (pin "60") (pinfunction "PD13_60") (pintype "passive"))
    )
    (net (code "59") (name "/P0_3") (class "Default")
      (node (ref "U18") (pin "1") (pinfunction "~{CS}_1") (pintype "passive"))
      (node (ref "U26") (pin "4") (pinfunction "P0_3_4") (pintype "passive"))
    )
    (net (code "60") (name "/P1_0") (class "Default")
      (node (ref "U26") (pin "22") (pinfunction "P1_0_22") (pintype "bidirectional"))
    )
    (net (code "61") (name "/P2_0") (class "Default")
      (node (ref "U26") (pin "40") (pinfunction "P2_0_40") (pintype "bidirectional"))
    )
    (net (code "62") (name "/P2_1") (class "Default")
      (node (ref "U26") (pin "8") (pinfunction "P2_1_8") (pintype "passive"))
    )
    (net (code "63") (name "/P2_2") (class "Default")
      (node (ref "U26") (pin "13") (pinfunction "P2_2_13") (pintype "passive"))
    )
    (net (code "64") (name "/P2_3") (class "Default")
      (node (ref "U26") (pin "18") (pinfunction "P2_3_18") (pintype "bidirectional"))
    )
    (net (code "65") (name "/P2_4") (class "Default")
      (node (ref "U26") (pin "20") (pinfunction "P2_4_20") (pintype "bidirectional"))
    )
    (net (code "66") (name "/P2_5") (class "Default")
      (node (ref "U26") (pin "32") (pinfunction "P2_5_32") (pintype "bidirectional"))
    )
    (net (code "67") (name "/P2_6") (class "Default")
      (node (ref "U26") (pin "33") (pinfunction "P2_6_33") (pintype "bidirectional"))
    )
    (net (code "68") (name "/P2_7") (class "Default")
      (node (ref "U26") (pin "36") (pinfunction "P2_7_36") (pintype "bidirectional"))
    )
    (net (code "69") (name "/P2_8") (class "Default")
      (node (ref "U26") (pin "37") (pinfunction "P2_8_37") (pintype "bidirectional"))
    )
    (net (code "70") (name "/P2_9") (class "Default")
      (node (ref "U26") (pin "39") (pinfunction "P2_9_39") (pintype "bidirectional"))
    )
    (net (code "71") (name "/PB3") (class "Default")
      (node (ref "U38") (pin "89") (pinfunction "PB3_89") (pintype "passive"))
    )
    (net (code "72") (name "/PB4") (class "Default")
      (node (ref "U38") (pin "90") (pinfunction "PB4_90") (pintype "passive"))
    )
    (net (code "73") (name "/PB5") (class "Default")
      (node (ref "U38") (pin "91") (pinfunction "PB5_91") (pintype "passive"))
    )
    (net (code "74") (name "/PWRCHK") (class "Default")
      (node (ref "U26") (pin "27") (pinfunction "P1_2_27") (pintype "bidirectional"))
    )
    (net (code "75") (name "/RST") (class "Default")
      (node (ref "U26") (pin "17") (pinfunction "RST_17") (pintype "passive"))
    )
    (net (code "76") (name "/SCLK") (class "Default")
      (node (ref "U18") (pin "6") (pinfunction "CLK_6") (pintype "passive"))
      (node (ref "U26") (pin "1") (pinfunction "P0_0_1") (pintype "passive"))
    )
    (net (code "77") (name "/STEP_1") (class "Default")
      (node (ref "U27") (pin "7") (pinfunction "STEP_7") (pintype "passive"))
      (node (ref "U38") (pin "43") (pinfunction "PE12_43") (pintype "passive"))
    )
    (net (code "78") (name "/STEP_2") (class "Default")
      (node (ref "U28") (pin "7") (pinfunction "STEP_7") (pintype "passive"))
      (node (ref "U38") (pin "37") (pinfunction "PB2_37") (pintype "passive"))
    )
    (net (code "79") (name "/STEP_3") (class "Default")
      (node (ref "U29") (pin "7") (pinfunction "STEP_7") (pintype "passive"))
      (node (ref "U38") (pin "85") (pinfunction "PD4_85") (pintype "passive"))
    )
    (net (code "80") (name "/STEP_4") (class "Default")
      (node (ref "U30") (pin "7") (pinfunction "STEP_7") (pintype "passive"))
      (node (ref "U38") (pin "47") (pinfunction "PB10_47") (pintype "passive"))
    )
    (net (code "81") (name "/STEP_5") (class "Default")
      (node (ref "U31") (pin "7") (pinfunction "STEP_7") (pintype "passive"))
      (node (ref "U38") (pin "56") (pinfunction "PD9_56") (pintype "passive"))
    )
    (net (code "82") (name "/STEP_6") (class "Default")
      (node (ref "U32") (pin "7") (pinfunction "STEP_7") (pintype "passive"))
      (node (ref "U38") (pin "51") (pinfunction "PB12_51") (pintype "passive"))
    )
    (net (code "83") (name "/STEP_7") (class "Default")
      (node (ref "U33") (pin "7") (pinfunction "STEP_7") (pintype "passive"))
      (node (ref "U38") (pin "66") (pinfunction "PC9_66") (pintype "passive"))
    )
    (net (code "84") (name "/STEP_8") (class "Default")
      (node (ref "U34") (pin "7") (pinfunction "STEP_7") (pintype "passive"))
      (node (ref "U38") (pin "61") (pinfunction "PD14_61") (pintype "passive"))
    )
    (net (code "85") (name "/SWCLK") (class "Default")
      (node (ref "J22") (pin "1") (pinfunction "1_1") (pintype "passive"))
      (node (ref "U38") (pin "76") (pinfunction "PA14_76") (pintype "passive"))
    )
    (net (code "86") (name "/SWDIO") (class "Default")
      (node (ref "J22") (pin "2") (pinfunction "2_2") (pintype "passive"))
      (node (ref "U38") (pin "72") (pinfunction "PA13_72") (pintype "passive"))
    )
    (net (code "87") (name "/VDCDC") (class "Default")
      (node (ref "C45") (pin "1") (pinfunction "1_1") (pintype "passive"))
      (node (ref "C69") (pin "1") (pinfunction "1_1") (pintype "passive"))
      (node (ref "L9") (pin "2") (pinfunction "2_2") (pintype "passive"))
      (node (ref "U26") (pin "19") (pinfunction "VDCDC_19") (pintype "bidirectional"))
      (node (ref "U26") (pin "31") (pinfunction "VDCDC_RF_31") (pintype "bidirectional"))
    )
    (net (code "88") (name "/XTAL_8M_1") (class "Default")
      (node (ref "C2") (pin "2") (pinfunction "2_2") (pintype "passive"))
      (node (ref "U38") (pin "12") (pinfunction "OSC_IN_12") (pintype "passive"))
      (node (ref "X1") (pin "2") (pinfunction "2_2") (pintype "passive"))
    )
    (net (code "89") (name "/XTAL_8M_2") (class "Default")
      (node (ref "C3") (pin "2") (pinfunction "2_2") (pintype "passive"))
      (node (ref "U38") (pin "13") (pinfunction "OSC_OUT_13") (pintype "passive"))
      (node (ref "X1") (pin "1") (pinfunction "1_1") (pintype "passive"))
    )
    (net (code "90") (name "/nRST") (class "Default")
      (node (ref "C4") (pin "2") (pinfunction "2_2") (pintype "passive"))
      (node (ref "K5") (pin "2") (pinfunction "2_2") (pintype "passive"))
      (node (ref "R1") (pin "2") (pinfunction "2_2") (pintype "passive"))
      (node (ref "U38") (pin "14") (pinfunction "NRST_14") (pintype "passive"))
    )
    (net (code "91") (name "DC24V") (class "Default")
      (node (ref "C73") (pin "1") (pinfunction "1_1") (pintype "passive"))
      (node (ref "C74") (pin "2") (pinfunction "2_2") (pintype "passive"))
      (node (ref "R38") (pin "2") (pinfunction "2_2") (pintype "passive"))
      (node (ref "TP11") (pin "1") (pinfunction "1_1") (pintype "passive"))
      (node (ref "TP24V") (pin "1") (pinfunction "1_1") (pintype "passive"))
      (node (ref "U27") (pin "16") (pinfunction "VMOT_16") (pintype "passive"))
      (node (ref "U28") (pin "16") (pinfunction "VMOT_16") (pintype "passive"))
      (node (ref "U29") (pin "16") (pinfunction "VMOT_16") (pintype "passive"))
      (node (ref "U30") (pin "16") (pinfunction "VMOT_16") (pintype "passive"))
      (node (ref "U31") (pin "16") (pinfunction "VMOT_16") (pintype "passive"))
      (node (ref "U32") (pin "16") (pinfunction "VMOT_16") (pintype "passive"))
      (node (ref "U33") (pin "16") (pinfunction "VMOT_16") (pintype "passive"))
      (node (ref "U34") (pin "16") (pinfunction "VMOT_16") (pintype "passive"))
      (node (ref "U36") (pin "7") (pinfunction "VIN_7") (pintype "passive"))
      (node (ref "U37") (pin "1") (pinfunction "Vin_1") (pintype "passive"))
    )
    (net (code "92") (name "GND") (class "Default")
      (node (ref "C15") (pin "1") (pinfunction "1_1") (pintype "passive"))
      (node (ref "C16") (pin "1") (pinfunction "1_1") (pintype "passive"))
      (node (ref "C17") (pin "2") (pinfunction "2_2") (pintype "passive"))
      (node (ref "C18") (pin "2") (pinfunction "2_2") (pintype "passive"))
      (node (ref "C2") (pin "1") (pinfunction "1_1") (pintype "passive"))
      (node (ref "C29") (pin "1") (pinfunction "1_1") (pintype "passive"))
      (node (ref "C3") (pin "1") (pinfunction "1_1") (pintype "passive"))
      (node (ref "C30") (pin "1") (pinfunction "1_1") (pintype "passive"))
      (node (ref "C31") (pin "1") (pinfunction "1_1") (pintype "passive"))
      (node (ref "C32") (pin "1") (pinfunction "1_1") (pintype "passive"))
      (node (ref "C4") (pin "1") (pinfunction "1_1") (pintype "passive"))
      (node (ref "C41") (pin "1") (pinfunction "1_1") (pintype "passive"))
      (node (ref "C42") (pin "1") (pinfunction "1_1") (pintype "passive"))
      (node (ref "C43") (pin "1") (pinfunction "1_1") (pintype "passive"))
      (node (ref "C44") (pin "2") (pinfunction "2_2") (pintype "passive"))
      (node (ref "C45") (pin "2") (pinfunction "2_2") (pintype "passive"))
      (node (ref "C5") (pin "1") (pinfunction "1_1") (pintype "passive"))
      (node (ref "C58") (pin "1") (pinfunction "1_1") (pintype "passive"))
      (node (ref "C6") (pin "1") (pinfunction "1_1") (pintype "passive"))
      (node (ref "C60") (pin "1") (pinfunction "1_1") (pintype "passive"))
      (node (ref "C62") (pin "1") (pinfunction "1_1") (pintype "passive"))
      (node (ref "C63") (pin "1") (pinfunction "1_1") (pintype "passive"))
      (node (ref "C65") (pin "2") (pinfunction "2_2") (pintype "passive"))
      (node (ref "C67") (pin "1") (pinfunction "1_1") (pintype "passive"))
      (node (ref "C68") (pin "1") (pinfunction "1_1") (pintype "passive"))
      (node (ref "C69") (pin "2") (pinfunction "2_2") (pintype "passive"))
      (node (ref "C73") (pin "2") (pinfunction "2_2") (pintype "passive"))
      (node (ref "C74") (pin "1") (pinfunction "1_1") (pintype "passive"))
      (node (ref "C75") (pin "1") (pinfunction "1_1") (pintype "passive"))
      (node (ref "C76") (pin "1") (pinfunction "1_1") (pintype "passive"))
      (node (ref "C77") (pin "1") (pinfunction "1_1") (pintype "passive"))
      (node (ref "C78") (pin "1") (pinfunction "1_1") (pintype "passive"))
      (node (ref "C79") (pin "1") (pinfunction "1_1") (pintype "passive"))
      (node (ref "C8") (pin "1") (pinfunction "1_1") (pintype "passive"))
      (node (ref "C80") (pin "1") (pinfunction "1_1") (pintype "passive"))
      (node (ref "C81") (pin "1") (pinfunction "1_1") (pintype "passive"))
      (node (ref "C9") (pin "1") (pinfunction "1_1") (pintype "passive"))
      (node (ref "D1") (pin "1") (pinfunction "1_1") (pintype "passive"))
      (node (ref "D2") (pin "2") (pinfunction "2_2") (pintype "passive"))
      (node (ref "D3") (pin "2") (pinfunction "2_2") (pintype "passive"))
      (node (ref "J22") (pin "4") (pinfunction "4_4") (pintype "passive"))
      (node (ref "J23") (pin "4") (pinfunction "4_4") (pintype "passive"))
      (node (ref "J24") (pin "3") (pinfunction "3_3") (pintype "passive"))
      (node (ref "J25") (pin "3") (pinfunction "3_3") (pintype "passive"))
      (node (ref "J26") (pin "3") (pinfunction "3_3") (pintype "passive"))
      (node (ref "J27") (pin "3") (pinfunction "3_3") (pintype "passive"))
      (node (ref "J28") (pin "2") (pinfunction "2_2") (pintype "passive"))
      (node (ref "J29") (pin "2") (pinfunction "2_2") (pintype "passive"))
      (node (ref "J30") (pin "2") (pinfunction "2_2") (pintype "passive"))
      (node (ref "J31") (pin "2") (pinfunction "2_2") (pintype "passive"))
      (node (ref "K1") (pin "1") (pinfunction "1_1") (pintype "passive"))
      (node (ref "K2") (pin "1") (pinfunction "1_1") (pintype "passive"))
      (node (ref "K3") (pin "1") (pinfunction "1_1") (pintype "passive"))
      (node (ref "K4") (pin "1") (pinfunction "1_1") (pintype "passive"))
      (node (ref "K5") (pin "1") (pinfunction "1_1") (pintype "passive"))
      (node (ref "R35") (pin "2") (pinfunction "2_2") (pintype "passive"))
      (node (ref "R37") (pin "1") (pinfunction "1_1") (pintype "passive"))
      (node (ref "TPGND") (pin "1") (pinfunction "1_1") (pintype "passive"))
      (node (ref "U12") (pin "1") (pinfunction "CLKIN_1") (pintype "passive"))
      (node (ref "U12") (pin "11") (pinfunction "FSYNC_11") (pintype "passive"))
      (node (ref "U12") (pin "18") (pinfunction "GND_18") (pintype "passive"))
      (node (ref "U12") (pin "9") (pinfunction "AD0_9") (pintype "passive"))
      (node (ref "U18") (pin "4") (pinfunction "GND_4") (pintype "passive"))
      (node (ref "U2") (pin "2") (pinfunction "GND_2") (pintype "passive"))
      (node (ref "U26") (pin "16") (pinfunction "GND_16") (pintype "power_in"))
      (node (ref "U26") (pin "23") (pinfunction "VBAT1V_23") (pintype "bidirectional"))
      (node (ref "U26") (pin "34") (pinfunction "RFIOm_34") (pintype "bidirectional"))
      (node (ref "U26") (pin "35") (pinfunction "RFIOp_35") (pintype "bidirectional"))
      (node (ref "U26") (pin "41") (pinfunction "THERM_PAD_41") (pintype "bidirectional"))
      (node (ref "U27") (pin "1") (pinfunction "~{EN}_1") (pintype "passive"))
      (node (ref "U27") (pin "15") (pinfunction "GND_15") (pintype "power_in"))
      (node (ref "U27") (pin "9") (pinfunction "GND_9") (pintype "power_in"))
      (node (ref "U28") (pin "1") (pinfunction "~{EN}_1") (pintype "passive"))
      (node (ref "U28") (pin "15") (pinfunction "GND_15") (pintype "power_in"))
      (node (ref "U28") (pin "9") (pinfunction "GND_9") (pintype "power_in"))
      (node (ref "U29") (pin "1") (pinfunction "~{EN}_1") (pintype "passive"))
      (node (ref "U29") (pin "15") (pinfunction "GND_15") (pintype "power_in"))
      (node (ref "U29") (pin "9") (pinfunction "GND_9") (pintype "power_in"))
      (node (ref "U30") (pin "1") (pinfunction "~{EN}_1") (pintype "passive"))
      (node (ref "U30") (pin "15") (pinfunction "GND_15") (pintype "power_in"))
      (node (ref "U30") (pin "9") (pinfunction "GND_9") (pintype "power_in"))
      (node (ref "U31") (pin "1") (pinfunction "~{EN}_1") (pintype "passive"))
      (node (ref "U31") (pin "15") (pinfunction "GND_15") (pintype "power_in"))
      (node (ref "U31") (pin "9") (pinfunction "GND_9") (pintype "power_in"))
      (node (ref "U32") (pin "1") (pinfunction "~{EN}_1") (pintype "passive"))
      (node (ref "U32") (pin "15") (pinfunction "GND_15") (pintype "power_in"))
      (node (ref "U32") (pin "9") (pinfunction "GND_9") (pintype "power_in"))
      (node (ref "U33") (pin "1") (pinfunction "~{EN}_1") (pintype "passive"))
      (node (ref "U33") (pin "15") (pinfunction "GND_15") (pintype "power_in"))
      (node (ref "U33") (pin "9") (pinfunction "GND_9") (pintype "power_in"))
      (node (ref "U34") (pin "1") (pinfunction "~{EN}_1") (pintype "passive"))
      (node (ref "U34") (pin "15") (pinfunction "GND_15") (pintype "power_in"))
      (node (ref "U34") (pin "9") (pinfunction "GND_9") (pintype "power_in"))
      (node (ref "U36") (pin "6") (pinfunction "GND_6") (pintype "passive"))
      (node (ref "U36") (pin "9") (pinfunction "PwPd_9") (pintype "passive"))
      (node (ref "U37") (pin "2") (pinfunction "GND_2") (pintype "passive"))
      (node (ref "U38") (pin "10") (pinfunction "VSS_5_10") (pintype "power_in"))
      (node (ref "U38") (pin "19") (pinfunction "VSSA_19") (pintype "power_in"))
      (node (ref "U38") (pin "20") (pinfunction "VREF-_20") (pintype "passive"))
      (node (ref "U38") (pin "27") (pinfunction "VSS_4_27") (pintype "power_in"))
      (node (ref "U38") (pin "49") (pinfunction "VSS_1_49") (pintype "power_in"))
      (node (ref "U38") (pin "74") (pinfunction "VSS_2_74") (pintype "passive"))
      (node (ref "U38") (pin "99") (pinfunction "VSS_3_99") (pintype "passive"))
      (node (ref "U39") (pin "11") (pinfunction "GND_11") (pintype "power_in"))
      (node (ref "U39") (pin "9") (pinfunction "GND_9") (pintype "power_in"))
      (node (ref "U4") (pin "2") (pinfunction "GND_2") (pintype "passive"))
      (node (ref "Y1") (pin "2") (pinfunction "2_2") (pintype "passive"))
      (node (ref "Y1") (pin "4") (pinfunction "4_4") (pintype "passive"))
    )
    (net (code "93") (name "Net-(D2-Pad1)") (class "Default")
      (node (ref "D2") (pin "1") (pinfunction "1_1") (pintype "passive"))
      (node (ref "R38") (pin "1") (pinfunction "1_1") (pintype "passive"))
    )
    (net (code "94") (name "Net-(D3-Pad1)") (class "Default")
      (node (ref "D3") (pin "1") (pinfunction "1_1") (pintype "passive"))
      (node (ref "R39") (pin "1") (pinfunction "1_1") (pintype "passive"))
    )
    (net (code "95") (name "Net-(U12-CPOUT)") (class "Default")
      (node (ref "C18") (pin "1") (pinfunction "1_1") (pintype "passive"))
      (node (ref "U12") (pin "20") (pinfunction "CPOUT_20") (pintype "passive"))
    )
    (net (code "96") (name "Net-(U12-REGOUT)") (class "Default")
      (node (ref "C16") (pin "2") (pinfunction "2_2") (pintype "passive"))
      (node (ref "U12") (pin "10") (pinfunction "REGOUT_10") (pintype "passive"))
    )
    (net (code "97") (name "Net-(U12-VDD)") (class "Default")
      (node (ref "R23") (pin "2") (pinfunction "2_2") (pintype "passive"))
      (node (ref "U12") (pin "13") (pinfunction "VDD_13") (pintype "passive"))
    )
    (net (code "98") (name "Net-(U26-SWITCH)") (class "Default")
      (node (ref "L9") (pin "1") (pinfunction "1_1") (pintype "passive"))
      (node (ref "U26") (pin "21") (pinfunction "SWITCH_21") (pintype "bidirectional"))
    )
    (net (code "99") (name "Net-(U26-XTAL16Mm)") (class "Default")
      (node (ref "U26") (pin "30") (pinfunction "XTAL16Mm_30") (pintype "bidirectional"))
      (node (ref "Y1") (pin "3") (pinfunction "3_3") (pintype "passive"))
    )
    (net (code "100") (name "Net-(U26-XTAL16Mp)") (class "Default")
      (node (ref "U26") (pin "29") (pinfunction "XTAL16Mp_29") (pintype "bidirectional"))
      (node (ref "Y1") (pin "1") (pinfunction "1_1") (pintype "passive"))
    )
    (net (code "101") (name "Net-(U26-XTAL32Km)") (class "Default")
      (node (ref "U26") (pin "11") (pinfunction "XTAL32Km_11") (pintype "passive"))
      (node (ref "X2") (pin "2") (pinfunction "2_2") (pintype "passive"))
    )
    (net (code "102") (name "Net-(U26-XTAL32Kp)") (class "Default")
      (node (ref "U26") (pin "12") (pinfunction "XTAL32Kp_12") (pintype "passive"))
      (node (ref "X2") (pin "1") (pinfunction "1_1") (pintype "passive"))
    )
    (net (code "103") (name "Net-(U27-1A)") (class "Default")
      (node (ref "J14") (pin "3") (pinfunction "3_3") (pintype "passive"))
      (node (ref "U27") (pin "12") (pinfunction "1A_12") (pintype "passive"))
    )
    (net (code "104") (name "Net-(U27-1B)") (class "Default")
      (node (ref "J14") (pin "4") (pinfunction "4_4") (pintype "passive"))
      (node (ref "U27") (pin "11") (pinfunction "1B_11") (pintype "passive"))
    )
    (net (code "105") (name "Net-(U27-2A)") (class "Default")
      (node (ref "J14") (pin "1") (pinfunction "1_1") (pintype "passive"))
      (node (ref "U27") (pin "14") (pinfunction "2A_14") (pintype "passive"))
    )
    (net (code "106") (name "Net-(U27-2B)") (class "Default")
      (node (ref "J14") (pin "2") (pinfunction "2_2") (pintype "passive"))
      (node (ref "U27") (pin "13") (pinfunction "2B_13") (pintype "passive"))
    )
    (net (code "107") (name "Net-(U27-~{RST})") (class "Default")
      (node (ref "U27") (pin "5") (pinfunction "~{RST}_5") (pintype "passive"))
      (node (ref "U27") (pin "6") (pinfunction "~{SLP}_6") (pintype "passive"))
    )
    (net (code "108") (name "Net-(U28-1A)") (class "Default")
      (node (ref "J15") (pin "3") (pinfunction "3_3") (pintype "passive"))
      (node (ref "U28") (pin "12") (pinfunction "1A_12") (pintype "passive"))
    )
    (net (code "109") (name "Net-(U28-1B)") (class "Default")
      (node (ref "J15") (pin "4") (pinfunction "4_4") (pintype "passive"))
      (node (ref "U28") (pin "11") (pinfunction "1B_11") (pintype "passive"))
    )
    (net (code "110") (name "Net-(U28-2A)") (class "Default")
      (node (ref "J15") (pin "1") (pinfunction "1_1") (pintype "passive"))
      (node (ref "U28") (pin "14") (pinfunction "2A_14") (pintype "passive"))
    )
    (net (code "111") (name "Net-(U28-2B)") (class "Default")
      (node (ref "J15") (pin "2") (pinfunction "2_2") (pintype "passive"))
      (node (ref "U28") (pin "13") (pinfunction "2B_13") (pintype "passive"))
    )
    (net (code "112") (name "Net-(U28-~{RST})") (class "Default")
      (node (ref "U28") (pin "5") (pinfunction "~{RST}_5") (pintype "passive"))
      (node (ref "U28") (pin "6") (pinfunction "~{SLP}_6") (pintype "passive"))
    )
    (net (code "113") (name "Net-(U29-1A)") (class "Default")
      (node (ref "J16") (pin "3") (pinfunction "3_3") (pintype "passive"))
      (node (ref "U29") (pin "12") (pinfunction "1A_12") (pintype "passive"))
    )
    (net (code "114") (name "Net-(U29-1B)") (class "Default")
      (node (ref "J16") (pin "4") (pinfunction "4_4") (pintype "passive"))
      (node (ref "U29") (pin "11") (pinfunction "1B_11") (pintype "passive"))
    )
    (net (code "115") (name "Net-(U29-2A)") (class "Default")
      (node (ref "J16") (pin "1") (pinfunction "1_1") (pintype "passive"))
      (node (ref "U29") (pin "14") (pinfunction "2A_14") (pintype "passive"))
    )
    (net (code "116") (name "Net-(U29-2B)") (class "Default")
      (node (ref "J16") (pin "2") (pinfunction "2_2") (pintype "passive"))
      (node (ref "U29") (pin "13") (pinfunction "2B_13") (pintype "passive"))
    )
    (net (code "117") (name "Net-(U29-~{RST})") (class "Default")
      (node (ref "U29") (pin "5") (pinfunction "~{RST}_5") (pintype "passive"))
      (node (ref "U29") (pin "6") (pinfunction "~{SLP}_6") (pintype "passive"))
    )
    (net (code "118") (name "Net-(U30-1A)") (class "Default")
      (node (ref "J17") (pin "3") (pinfunction "3_3") (pintype "passive"))
      (node (ref "U30") (pin "12") (pinfunction "1A_12") (pintype "passive"))
    )
    (net (code "119") (name "Net-(U30-1B)") (class "Default")
      (node (ref "J17") (pin "4") (pinfunction "4_4") (pintype "passive"))
      (node (ref "U30") (pin "11") (pinfunction "1B_11") (pintype "passive"))
    )
    (net (code "120") (name "Net-(U30-2A)") (class "Default")
      (node (ref "J17") (pin "1") (pinfunction "1_1") (pintype "passive"))
      (node (ref "U30") (pin "14") (pinfunction "2A_14") (pintype "passive"))
    )
    (net (code "121") (name "Net-(U30-2B)") (class "Default")
      (node (ref "J17") (pin "2") (pinfunction "2_2") (pintype "passive"))
      (node (ref "U30") (pin "13") (pinfunction "2B_13") (pintype "passive"))
    )
    (net (code "122") (name "Net-(U30-~{RST})") (class "Default")
      (node (ref "U30") (pin "5") (pinfunction "~{RST}_5") (pintype "passive"))
      (node (ref "U30") (pin "6") (pinfunction "~{SLP}_6") (pintype "passive"))
    )
    (net (code "123") (name "Net-(U31-1A)") (class "Default")
      (node (ref "J18") (pin "3") (pinfunction "3_3") (pintype "passive"))
      (node (ref "U31") (pin "12") (pinfunction "1A_12") (pintype "passive"))
    )
    (net (code "124") (name "Net-(U31-1B)") (class "Default")
      (node (ref "J18") (pin "4") (pinfunction "4_4") (pintype "passive"))
      (node (ref "U31") (pin "11") (pinfunction "1B_11") (pintype "passive"))
    )
    (net (code "125") (name "Net-(U31-2A)") (class "Default")
      (node (ref "J18") (pin "1") (pinfunction "1_1") (pintype "passive"))
      (node (ref "U31") (pin "14") (pinfunction "2A_14") (pintype "passive"))
    )
    (net (code "126") (name "Net-(U31-2B)") (class "Default")
      (node (ref "J18") (pin "2") (pinfunction "2_2") (pintype "passive"))
      (node (ref "U31") (pin "13") (pinfunction "2B_13") (pintype "passive"))
    )
    (net (code "127") (name "Net-(U31-~{RST})") (class "Default")
      (node (ref "U31") (pin "5") (pinfunction "~{RST}_5") (pintype "passive"))
      (node (ref "U31") (pin "6") (pinfunction "~{SLP}_6") (pintype "passive"))
    )
    (net (code "128") (name "Net-(U32-1A)") (class "Default")
      (node (ref "J19") (pin "3") (pinfunction "3_3") (pintype "passive"))
      (node (ref "U32") (pin "12") (pinfunction "1A_12") (pintype "passive"))
    )
    (net (code "129") (name "Net-(U32-1B)") (class "Default")
      (node (ref "J19") (pin "4") (pinfunction "4_4") (pintype "passive"))
      (node (ref "U32") (pin "11") (pinfunction "1B_11") (pintype "passive"))
    )
    (net (code "130") (name "Net-(U32-2A)") (class "Default")
      (node (ref "J19") (pin "1") (pinfunction "1_1") (pintype "passive"))
      (node (ref "U32") (pin "14") (pinfunction "2A_14") (pintype "passive"))
    )
    (net (code "131") (name "Net-(U32-2B)") (class "Default")
      (node (ref "J19") (pin "2") (pinfunction "2_2") (pintype "passive"))
      (node (ref "U32") (pin "13") (pinfunction "2B_13") (pintype "passive"))
    )
    (net (code "132") (name "Net-(U32-~{RST})") (class "Default")
      (node (ref "U32") (pin "5") (pinfunction "~{RST}_5") (pintype "passive"))
      (node (ref "U32") (pin "6") (pinfunction "~{SLP}_6") (pintype "passive"))
    )
    (net (code "133") (name "Net-(U33-1A)") (class "Default")
      (node (ref "J20") (pin "3") (pinfunction "3_3") (pintype "passive"))
      (node (ref "U33") (pin "12") (pinfunction "1A_12") (pintype "passive"))
    )
    (net (code "134") (name "Net-(U33-1B)") (class "Default")
      (node (ref "J20") (pin "4") (pinfunction "4_4") (pintype "passive"))
      (node (ref "U33") (pin "11") (pinfunction "1B_11") (pintype "passive"))
    )
    (net (code "135") (name "Net-(U33-2A)") (class "Default")
      (node (ref "J20") (pin "1") (pinfunction "1_1") (pintype "passive"))
      (node (ref "U33") (pin "14") (pinfunction "2A_14") (pintype "passive"))
    )
    (net (code "136") (name "Net-(U33-2B)") (class "Default")
      (node (ref "J20") (pin "2") (pinfunction "2_2") (pintype "passive"))
      (node (ref "U33") (pin "13") (pinfunction "2B_13") (pintype "passive"))
    )
    (net (code "137") (name "Net-(U33-~{RST})") (class "Default")
      (node (ref "U33") (pin "5") (pinfunction "~{RST}_5") (pintype "passive"))
      (node (ref "U33") (pin "6") (pinfunction "~{SLP}_6") (pintype "passive"))
    )
    (net (code "138") (name "Net-(U34-1A)") (class "Default")
      (node (ref "J21") (pin "3") (pinfunction "3_3") (pintype "passive"))
      (node (ref "U34") (pin "12") (pinfunction "1A_12") (pintype "passive"))
    )
    (net (code "139") (name "Net-(U34-1B)") (class "Default")
      (node (ref "J21") (pin "4") (pinfunction "4_4") (pintype "passive"))
      (node (ref "U34") (pin "11") (pinfunction "1B_11") (pintype "passive"))
    )
    (net (code "140") (name "Net-(U34-2A)") (class "Default")
      (node (ref "J21") (pin "1") (pinfunction "1_1") (pintype "passive"))
      (node (ref "U34") (pin "14") (pinfunction "2A_14") (pintype "passive"))
    )
    (net (code "141") (name "Net-(U34-2B)") (class "Default")
      (node (ref "J21") (pin "2") (pinfunction "2_2") (pintype "passive"))
      (node (ref "U34") (pin "13") (pinfunction "2B_13") (pintype "passive"))
    )
    (net (code "142") (name "Net-(U34-~{RST})") (class "Default")
      (node (ref "U34") (pin "5") (pinfunction "~{RST}_5") (pintype "passive"))
      (node (ref "U34") (pin "6") (pinfunction "~{SLP}_6") (pintype "passive"))
    )
    (net (code "143") (name "Net-(U36-BOOT)") (class "Default")
      (node (ref "C70") (pin "1") (pinfunction "1_1") (pintype "passive"))
      (node (ref "U36") (pin "1") (pinfunction "BOOT_1") (pintype "passive"))
    )
    (net (code "144") (name "Net-(U36-PH)") (class "Default")
      (node (ref "C70") (pin "2") (pinfunction "2_2") (pintype "passive"))
      (node (ref "D1") (pin "2") (pinfunction "2_2") (pintype "passive"))
      (node (ref "L10") (pin "1") (pinfunction "1_1") (pintype "passive"))
      (node (ref "U36") (pin "8") (pinfunction "PH_8") (pintype "passive"))
    )
    (net (code "145") (name "Net-(U36-VSNS)") (class "Default")
      (node (ref "R36") (pin "1") (pinfunction "1_1") (pintype "passive"))
      (node (ref "R37") (pin "2") (pinfunction "2_2") (pintype "passive"))
      (node (ref "U36") (pin "4") (pinfunction "VSNS_4") (pintype "passive"))
    )
    (net (code "146") (name "Net-(U39-C1)") (class "Default")
      (node (ref "C65") (pin "1") (pinfunction "1_1") (pintype "passive"))
      (node (ref "U39") (pin "10") (pinfunction "C1_10") (pintype "passive"))
    )
    (net (code "147") (name "Net-(U39-SETC)") (class "Default")
      (node (ref "C64") (pin "2") (pinfunction "2_2") (pintype "passive"))
      (node (ref "U39") (pin "12") (pinfunction "SETC_12") (pintype "passive"))
    )
    (net (code "148") (name "Net-(U39-STEP)") (class "Default")
      (node (ref "C64") (pin "1") (pinfunction "1_1") (pintype "passive"))
      (node (ref "U39") (pin "8") (pinfunction "STEP_8") (pintype "passive"))
    )
    (net (code "149") (name "VCC_5V") (class "Default")
      (node (ref "C31") (pin "2") (pinfunction "2_2") (pintype "passive"))
      (node (ref "C32") (pin "2") (pinfunction "2_2") (pintype "passive"))
      (node (ref "C5") (pin "2") (pinfunction "2_2") (pintype "passive"))
      (node (ref "C58") (pin "2") (pinfunction "2_2") (pintype "passive"))
      (node (ref "C60") (pin "2") (pinfunction "2_2") (pintype "passive"))
      (node (ref "C75") (pin "2") (pinfunction "2_2") (pintype "passive"))
      (node (ref "C8") (pin "2") (pinfunction "2_2") (pintype "passive"))
      (node (ref "L10") (pin "2") (pinfunction "2_2") (pintype "passive"))
      (node (ref "R36") (pin "2") (pinfunction "2_2") (pintype "passive"))
      (node (ref "R39") (pin "2") (pinfunction "2_2") (pintype "passive"))
      (node (ref "U2") (pin "1") (pinfunction "VIN_1") (pintype "passive"))
      (node (ref "U2") (pin "3") (pinfunction "EN_3") (pintype "passive"))
      (node (ref "U4") (pin "1") (pinfunction "VIN_1") (pintype "passive"))
      (node (ref "U4") (pin "3") (pinfunction "EN_3") (pintype "passive"))
    )
    (net (code "150") (name "VDD3V3_BLE") (class "Default")
      (node (ref "C30") (pin "2") (pinfunction "2_2") (pintype "passive"))
      (node (ref "C44") (pin "1") (pinfunction "1_1") (pintype "passive"))
      (node (ref "C9") (pin "2") (pinfunction "2_2") (pintype "passive"))
      (node (ref "J23") (pin "3") (pinfunction "3_3") (pintype "passive"))
      (node (ref "TPBLE") (pin "1") (pinfunction "1_1") (pintype "passive"))
      (node (ref "U18") (pin "3") (pinfunction "~{WP}_3") (pintype "passive"))
      (node (ref "U18") (pin "7") (pinfunction "~{HOLD}_7") (pintype "passive"))
      (node (ref "U18") (pin "8") (pinfunction "VCC_8") (pintype "passive"))
      (node (ref "U26") (pin "14") (pinfunction "VBAT_RF_14") (pintype "passive"))
      (node (ref "U26") (pin "15") (pinfunction "VBAT3V_15") (pintype "passive"))
      (node (ref "U4") (pin "5") (pinfunction "VOUT_5") (pintype "passive"))
    )
    (net (code "151") (name "VDD3V3_MCU") (class "Default")
      (node (ref "C15") (pin "2") (pinfunction "2_2") (pintype "passive"))
      (node (ref "C17") (pin "1") (pinfunction "1_1") (pintype "passive"))
      (node (ref "C29") (pin "2") (pinfunction "2_2") (pintype "passive"))
      (node (ref "C41") (pin "2") (pinfunction "2_2") (pintype "passive"))
      (node (ref "C42") (pin "2") (pinfunction "2_2") (pintype "passive"))
      (node (ref "C43") (pin "2") (pinfunction "2_2") (pintype "passive"))
      (node (ref "C6") (pin "2") (pinfunction "2_2") (pintype "passive"))
      (node (ref "C62") (pin "2") (pinfunction "2_2") (pintype "passive"))
      (node (ref "C63") (pin "2") (pinfunction "2_2") (pintype "passive"))
      (node (ref "C76") (pin "2") (pinfunction "2_2") (pintype "passive"))
      (node (ref "C77") (pin "2") (pinfunction "2_2") (pintype "passive"))
      (node (ref "J22") (pin "3") (pinfunction "3_3") (pintype "passive"))
      (node (ref "J24") (pin "1") (pinfunction "1_1") (pintype "passive"))
      (node (ref "J25") (pin "1") (pinfunction "1_1") (pintype "passive"))
      (node (ref "J26") (pin "1") (pinfunction "1_1") (pintype "passive"))
      (node (ref "J27") (pin "1") (pinfunction "1_1") (pintype "passive"))
      (node (ref "R1") (pin "1") (pinfunction "1_1") (pintype "passive"))
      (node (ref "R23") (pin "1") (pinfunction "1_1") (pintype "passive"))
      (node (ref "R40") (pin "2") (pinfunction "2_2") (pintype "passive"))
      (node (ref "R41") (pin "2") (pinfunction "2_2") (pintype "passive"))
      (node (ref "R43") (pin "2") (pinfunction "2_2") (pintype "passive"))
      (node (ref "R45") (pin "2") (pinfunction "2_2") (pintype "passive"))
      (node (ref "R47") (pin "2") (pinfunction "2_2") (pintype "passive"))
      (node (ref "R49") (pin "2") (pinfunction "2_2") (pintype "passive"))
      (node (ref "R51") (pin "2") (pinfunction "2_2") (pintype "passive"))
      (node (ref "R53") (pin "2") (pinfunction "2_2") (pintype "passive"))
      (node (ref "R55") (pin "2") (pinfunction "2_2") (pintype "passive"))
      (node (ref "R56") (pin "2") (pinfunction "2_2") (pintype "passive"))
      (node (ref "R57") (pin "2") (pinfunction "2_2") (pintype "passive"))
      (node (ref "R58") (pin "1") (pinfunction "1_1") (pintype "passive"))
      (node (ref "R59") (pin "2") (pinfunction "2_2") (pintype "passive"))
      (node (ref "R60") (pin "2") (pinfunction "2_2") (pintype "passive"))
      (node (ref "R61") (pin "2") (pinfunction "2_2") (pintype "passive"))
      (node (ref "R62") (pin "2") (pinfunction "2_2") (pintype "passive"))
      (node (ref "TP3V3") (pin "1") (pinfunction "1_1") (pintype "passive"))
      (node (ref "U12") (pin "8") (pinfunction "VLOGIC_8") (pintype "passive"))
      (node (ref "U2") (pin "5") (pinfunction "VOUT_5") (pintype "passive"))
      (node (ref "U27") (pin "10") (pinfunction "VDD_10") (pintype "passive"))
      (node (ref "U28") (pin "10") (pinfunction "VDD_10") (pintype "passive"))
      (node (ref "U29") (pin "10") (pinfunction "VDD_10") (pintype "passive"))
      (node (ref "U30") (pin "10") (pinfunction "VDD_10") (pintype "passive"))
      (node (ref "U31") (pin "10") (pinfunction "VDD_10") (pintype "passive"))
      (node (ref "U32") (pin "10") (pinfunction "VDD_10") (pintype "passive"))
      (node (ref "U33") (pin "10") (pinfunction "VDD_10") (pintype "passive"))
      (node (ref "U34") (pin "10") (pinfunction "VDD_10") (pintype "passive"))
      (node (ref "U38") (pin "100") (pinfunction "VDD_3_100") (pintype "passive"))
      (node (ref "U38") (pin "11") (pinfunction "VDD_5_11") (pintype "power_in"))
      (node (ref "U38") (pin "21") (pinfunction "VREF+_21") (pintype "passive"))
      (node (ref "U38") (pin "22") (pinfunction "VDDA_22") (pintype "passive"))
      (node (ref "U38") (pin "28") (pinfunction "VDD_4_28") (pintype "power_in"))
      (node (ref "U38") (pin "50") (pinfunction "VDD_1_50") (pintype "power_in"))
      (node (ref "U38") (pin "6") (pinfunction "VBAT_6") (pintype "passive"))
      (node (ref "U38") (pin "75") (pinfunction "VDD_2_75") (pintype "passive"))
      (node (ref "U39") (pin "13") (pinfunction "VDDIO_13") (pintype "power_in"))
      (node (ref "U39") (pin "2") (pinfunction "VDD_2") (pintype "power_in"))
      (node (ref "U39") (pin "4") (pinfunction "S1_4") (pintype "passive"))
      (node (ref "U39") (pin "6") (pinfunction "NC_3_6") (pintype "passive"))
    )
    (net (code "152") (name "unconnected-(TP7-Pad1)") (class "Default")
      (node (ref "TP7") (pin "1") (pinfunction "1_1") (pintype "passive"))
    )
    (net (code "153") (name "unconnected-(TP8-Pad1)") (class "Default")
      (node (ref "TP8") (pin "1") (pinfunction "1_1") (pintype "passive"))
    )
    (net (code "154") (name "unconnected-(TP9-Pad1)") (class "Default")
      (node (ref "TP9") (pin "1") (pinfunction "1_1") (pintype "passive"))
    )
    (net (code "155") (name "unconnected-(TP10-Pad1)") (class "Default")
      (node (ref "TP10") (pin "1") (pinfunction "1_1") (pintype "passive"))
    )
    (net (code "156") (name "unconnected-(U2-NC-Pad4)") (class "Default")
      (node (ref "U2") (pin "4") (pinfunction "NC_4") (pintype "passive"))
    )
    (net (code "157") (name "unconnected-(U4-NC-Pad4)") (class "Default")
      (node (ref "U4") (pin "4") (pinfunction "NC_4") (pintype "passive"))
    )
    (net (code "158") (name "unconnected-(U12-AUXDA-Pad6)") (class "Default")
      (node (ref "U12") (pin "6") (pinfunction "AUXDA_6") (pintype "passive"))
    )
    (net (code "159") (name "unconnected-(U12-AUXDL-Pad7)") (class "Default")
      (node (ref "U12") (pin "7") (pinfunction "AUXDL_7") (pintype "passive"))
    )
    (net (code "160") (name "unconnected-(U12-NC_1-Pad2)") (class "Default")
      (node (ref "U12") (pin "2") (pinfunction "NC_1_2") (pintype "power_in"))
    )
    (net (code "161") (name "unconnected-(U12-NC_2-Pad3)") (class "Default")
      (node (ref "U12") (pin "3") (pinfunction "NC_2_3") (pintype "power_in"))
    )
    (net (code "162") (name "unconnected-(U12-NC_3-Pad4)") (class "Default")
      (node (ref "U12") (pin "4") (pinfunction "NC_3_4") (pintype "power_in"))
    )
    (net (code "163") (name "unconnected-(U12-NC_4-Pad5)") (class "Default")
      (node (ref "U12") (pin "5") (pinfunction "NC_4_5") (pintype "power_in"))
    )
    (net (code "164") (name "unconnected-(U12-NC_5-Pad14)") (class "Default")
      (node (ref "U12") (pin "14") (pinfunction "NC_5_14") (pintype "power_in"))
    )
    (net (code "165") (name "unconnected-(U12-NC_6-Pad15)") (class "Default")
      (node (ref "U12") (pin "15") (pinfunction "NC_6_15") (pintype "power_in"))
    )
    (net (code "166") (name "unconnected-(U12-NC_7-Pad16)") (class "Default")
      (node (ref "U12") (pin "16") (pinfunction "NC_7_16") (pintype "power_in"))
    )
    (net (code "167") (name "unconnected-(U12-NC_8-Pad17)") (class "Default")
      (node (ref "U12") (pin "17") (pinfunction "NC_8_17") (pintype "power_in"))
    )
    (net (code "168") (name "unconnected-(U12-RESV_1-Pad22)") (class "Default")
      (node (ref "U12") (pin "22") (pinfunction "RESV_1_22") (pintype "passive"))
    )
    (net (code "169") (name "unconnected-(U12-RESV_2-Pad21)") (class "Default")
      (node (ref "U12") (pin "21") (pinfunction "RESV_2_21") (pintype "passive"))
    )
    (net (code "170") (name "unconnected-(U12-RESV_3-Pad19)") (class "Default")
      (node (ref "U12") (pin "19") (pinfunction "RESV_3_19") (pintype "passive"))
    )
    (net (code "171") (name "unconnected-(U26-NC-Pad5)") (class "Default")
      (node (ref "U26") (pin "5") (pinfunction "NC_5") (pintype "passive"))
    )
    (net (code "172") (name "unconnected-(U26-P0_2-Pad3)") (class "Default")
      (node (ref "U26") (pin "3") (pinfunction "P0_2_3") (pintype "passive"))
    )
    (net (code "173") (name "unconnected-(U26-P1_1-Pad24)") (class "Default")
      (node (ref "U26") (pin "24") (pinfunction "P1_1_24") (pintype "bidirectional"))
    )
    (net (code "174") (name "unconnected-(U26-P1_3-Pad28)") (class "Default")
      (node (ref "U26") (pin "28") (pinfunction "P1_3_28") (pintype "bidirectional"))
    )
    (net (code "175") (name "unconnected-(U26-VPP-Pad38)") (class "Default")
      (node (ref "U26") (pin "38") (pinfunction "VPP_38") (pintype "bidirectional"))
    )
    (net (code "176") (name "unconnected-(U36-ENA-Pad5)") (class "Default")
      (node (ref "U36") (pin "5") (pinfunction "ENA_5") (pintype "passive"))
    )
    (net (code "177") (name "unconnected-(U36-NC_1-Pad2)") (class "Default")
      (node (ref "U36") (pin "2") (pinfunction "NC_1_2") (pintype "passive"))
    )
    (net (code "178") (name "unconnected-(U36-NC_2-Pad3)") (class "Default")
      (node (ref "U36") (pin "3") (pinfunction "NC_2_3") (pintype "passive"))
    )
    (net (code "179") (name "unconnected-(U37-Con-Pad3)") (class "Default")
      (node (ref "U37") (pin "3") (pinfunction "Con_3") (pintype "passive"))
    )
    (net (code "180") (name "unconnected-(U38-NC-Pad73)") (class "Default")
      (node (ref "U38") (pin "73") (pinfunction "NC_73") (pintype "passive"))
    )
    (net (code "181") (name "unconnected-(U38-PA4-Pad29)") (class "Default")
      (node (ref "U38") (pin "29") (pinfunction "PA4_29") (pintype "passive"))
    )
    (net (code "182") (name "unconnected-(U38-PA11-Pad70)") (class "Default")
      (node (ref "U38") (pin "70") (pinfunction "PA11_70") (pintype "passive"))
    )
    (net (code "183") (name "unconnected-(U38-PA12-Pad71)") (class "Default")
      (node (ref "U38") (pin "71") (pinfunction "PA12_71") (pintype "passive"))
    )
    (net (code "184") (name "unconnected-(U38-PC0-Pad15)") (class "Default")
      (node (ref "U38") (pin "15") (pinfunction "PC0_15") (pintype "passive"))
    )
    (net (code "185") (name "unconnected-(U38-PC1-Pad16)") (class "Default")
      (node (ref "U38") (pin "16") (pinfunction "PC1_16") (pintype "passive"))
    )
    (net (code "186") (name "unconnected-(U38-PC2-Pad17)") (class "Default")
      (node (ref "U38") (pin "17") (pinfunction "PC2_17") (pintype "passive"))
    )
    (net (code "187") (name "unconnected-(U38-PC3-Pad18)") (class "Default")
      (node (ref "U38") (pin "18") (pinfunction "PC3_18") (pintype "passive"))
    )
    (net (code "188") (name "unconnected-(U38-PC13-Pad7)") (class "Default")
      (node (ref "U38") (pin "7") (pinfunction "PC13_7") (pintype "passive"))
    )
    (net (code "189") (name "unconnected-(U38-PC14-Pad8)") (class "Default")
      (node (ref "U38") (pin "8") (pinfunction "PC14_8") (pintype "passive"))
    )
    (net (code "190") (name "unconnected-(U38-PC15-Pad9)") (class "Default")
      (node (ref "U38") (pin "9") (pinfunction "PC15_9") (pintype "passive"))
    )
    (net (code "191") (name "unconnected-(U38-PE0-Pad97)") (class "Default")
      (node (ref "U38") (pin "97") (pinfunction "PE0_97") (pintype "passive"))
    )
    (net (code "192") (name "unconnected-(U38-PE1-Pad98)") (class "Default")
      (node (ref "U38") (pin "98") (pinfunction "PE1_98") (pintype "passive"))
    )
    (net (code "193") (name "unconnected-(U38-PE2-Pad1)") (class "Default")
      (node (ref "U38") (pin "1") (pinfunction "PE2_1") (pintype "passive"))
    )
    (net (code "194") (name "unconnected-(U38-PE3-Pad2)") (class "Default")
      (node (ref "U38") (pin "2") (pinfunction "PE3_2") (pintype "passive"))
    )
    (net (code "195") (name "unconnected-(U38-PE4-Pad3)") (class "Default")
      (node (ref "U38") (pin "3") (pinfunction "PE4_3") (pintype "passive"))
    )
    (net (code "196") (name "unconnected-(U38-PE5-Pad4)") (class "Default")
      (node (ref "U38") (pin "4") (pinfunction "PE5_4") (pintype "passive"))
    )
    (net (code "197") (name "unconnected-(U38-PE6-Pad5)") (class "Default")
      (node (ref "U38") (pin "5") (pinfunction "PE6_5") (pintype "passive"))
    )
    (net (code "198") (name "unconnected-(U39-NC_1-Pad3)") (class "Default")
      (node (ref "U39") (pin "3") (pinfunction "NC_1_3") (pintype "passive"))
    )
    (net (code "199") (name "unconnected-(U39-NC_2-Pad5)") (class "Default")
      (node (ref "U39") (pin "5") (pinfunction "NC_2_5") (pintype "passive"))
    )
    (net (code "200") (name "unconnected-(U39-NC_4-Pad7)") (class "Default")
      (node (ref "U39") (pin "7") (pinfunction "NC_4_7") (pintype "passive"))
    )
    (net (code "201") (name "unconnected-(U39-NC_5-Pad14)") (class "Default")
      (node (ref "U39") (pin "14") (pinfunction "NC_5_14") (pintype "passive"))
    )
  )
)
